# Precision_Arduino_Charlieplex_1_1.net
KiCad netlist of a schematic drawn in EAGLE
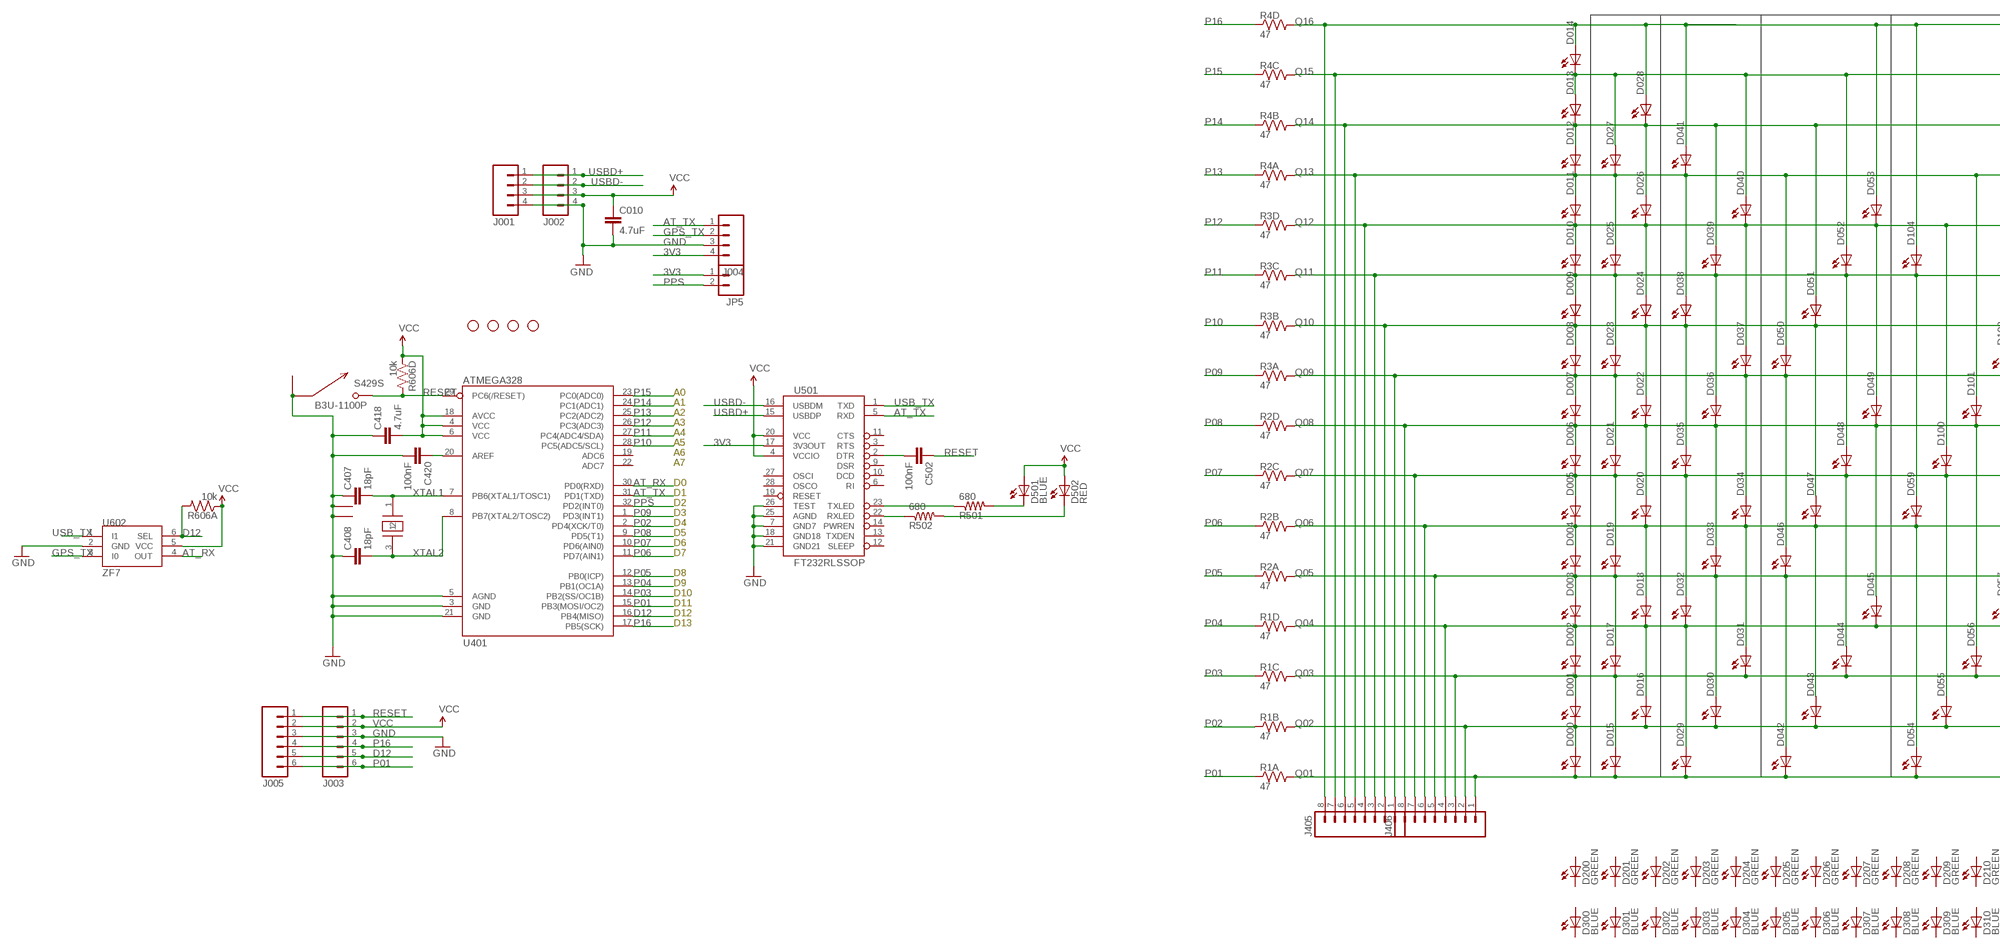
[diagram p0: schematic, sheet 1, part 1 of 2]
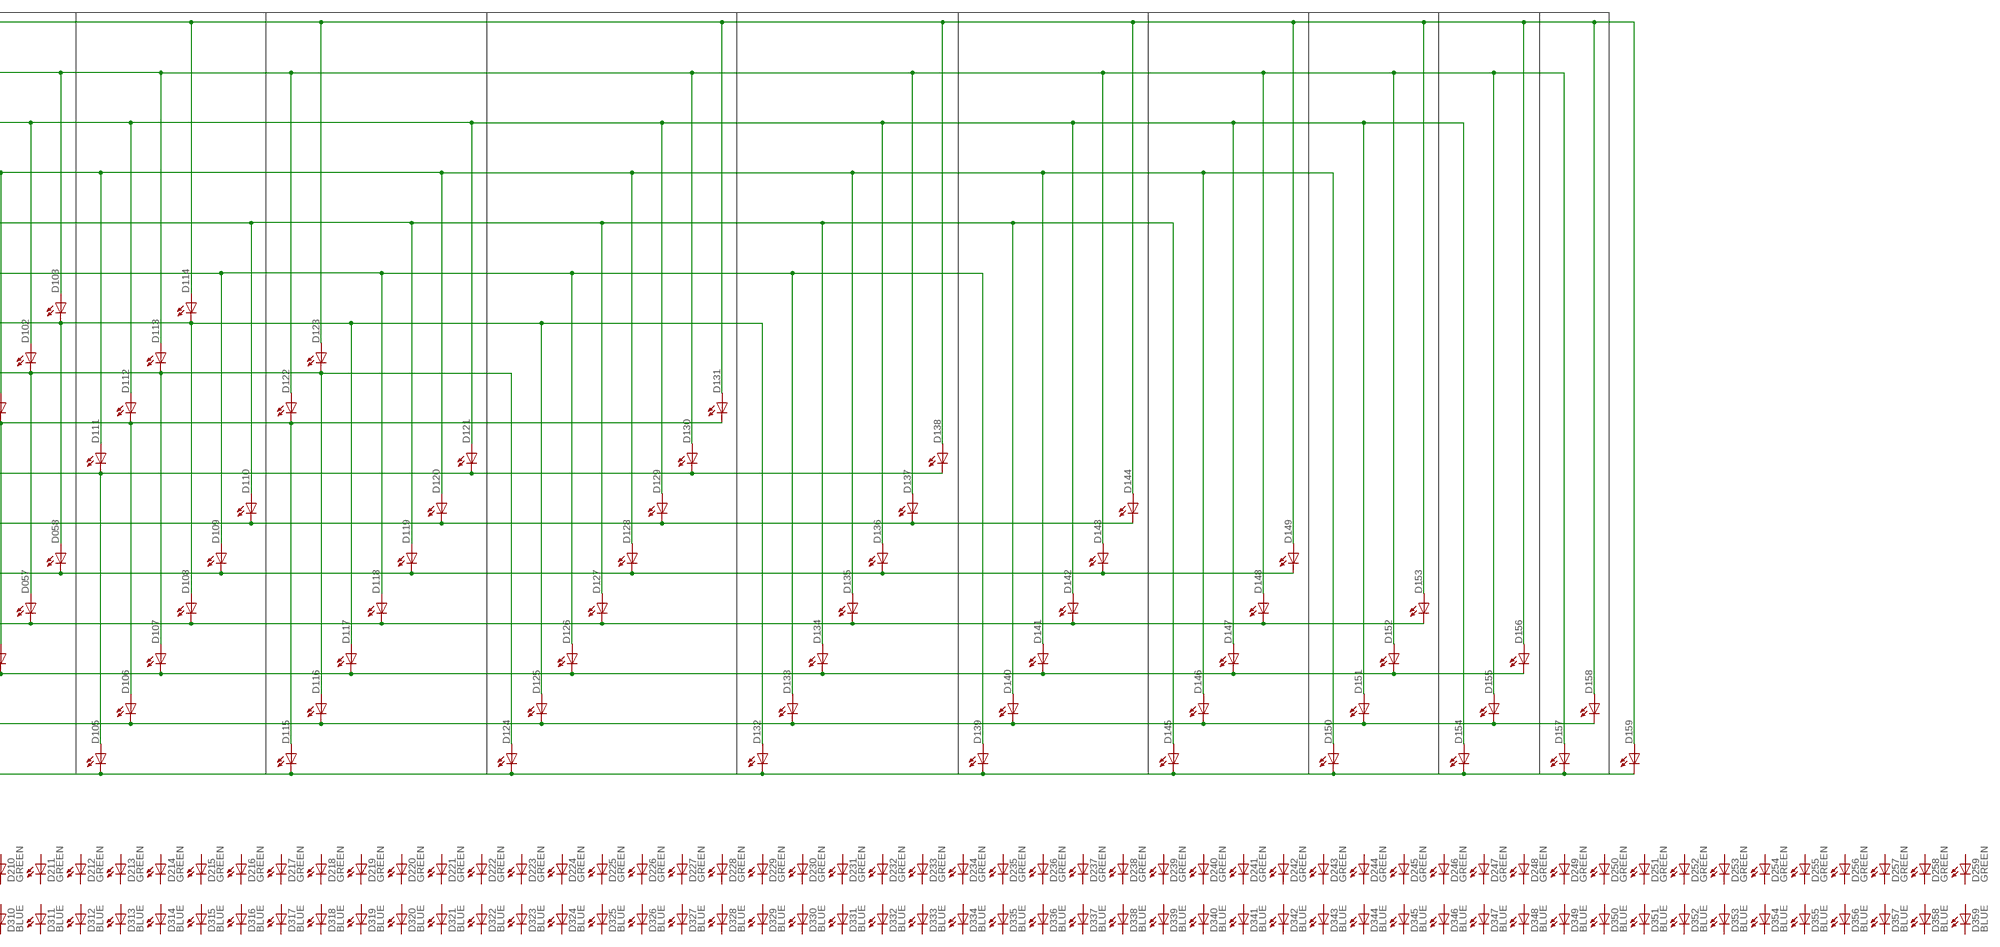
[diagram p1: schematic, sheet 1, part 2 of 2]

(export (version "E")
  (design (tool "Eeschema 10.0.6"))
  (components
    (comp (ref "C010")
      (value "4.7uF")
      (footprint "eagle-import:0603-CAP")
      (libsource (lib "eagle-import") (part "CAP0603-CAP"))
    )
    (comp (ref "C407")
      (value "18pF")
      (footprint "eagle-import:0603-CAP")
      (libsource (lib "eagle-import") (part "CAP0603-CAP"))
    )
    (comp (ref "C408")
      (value "18pF")
      (footprint "eagle-import:0603-CAP")
      (libsource (lib "eagle-import") (part "CAP0603-CAP"))
    )
    (comp (ref "C418")
      (value "4.7uF")
      (footprint "eagle-import:0603-CAP")
      (libsource (lib "eagle-import") (part "CAP0603-CAP"))
    )
    (comp (ref "C420")
      (value "100nF")
      (footprint "eagle-import:0603-CAP")
      (libsource (lib "eagle-import") (part "CAP0603-CAP"))
    )
    (comp (ref "C502")
      (value "100nF")
      (footprint "eagle-import:0603-CAP")
      (libsource (lib "eagle-import") (part "CAP0603-CAP"))
    )
    (comp (ref "D000")
      (value "RED")
      (footprint "eagle-import:LED-0603")
      (libsource (lib "eagle-import") (part "SparkFun-LED_LED0603"))
    )
    (comp (ref "D001")
      (value "RED")
      (footprint "eagle-import:LED-0603")
      (libsource (lib "eagle-import") (part "SparkFun-LED_LED0603"))
    )
    (comp (ref "D002")
      (value "RED")
      (footprint "eagle-import:LED-0603")
      (libsource (lib "eagle-import") (part "SparkFun-LED_LED0603"))
    )
    (comp (ref "D003")
      (value "RED")
      (footprint "eagle-import:LED-0603")
      (libsource (lib "eagle-import") (part "SparkFun-LED_LED0603"))
    )
    (comp (ref "D004")
      (value "RED")
      (footprint "eagle-import:LED-0603")
      (libsource (lib "eagle-import") (part "SparkFun-LED_LED0603"))
    )
    (comp (ref "D005")
      (value "RED")
      (footprint "eagle-import:LED-0603")
      (libsource (lib "eagle-import") (part "SparkFun-LED_LED0603"))
    )
    (comp (ref "D006")
      (value "RED")
      (footprint "eagle-import:LED-0603")
      (libsource (lib "eagle-import") (part "SparkFun-LED_LED0603"))
    )
    (comp (ref "D007")
      (value "RED")
      (footprint "eagle-import:LED-0603")
      (libsource (lib "eagle-import") (part "SparkFun-LED_LED0603"))
    )
    (comp (ref "D008")
      (value "RED")
      (footprint "eagle-import:LED-0603")
      (libsource (lib "eagle-import") (part "SparkFun-LED_LED0603"))
    )
    (comp (ref "D009")
      (value "RED")
      (footprint "eagle-import:LED-0603")
      (libsource (lib "eagle-import") (part "SparkFun-LED_LED0603"))
    )
    (comp (ref "D010")
      (value "RED")
      (footprint "eagle-import:LED-0603")
      (libsource (lib "eagle-import") (part "SparkFun-LED_LED0603"))
    )
    (comp (ref "D011")
      (value "RED")
      (footprint "eagle-import:LED-0603")
      (libsource (lib "eagle-import") (part "SparkFun-LED_LED0603"))
    )
    (comp (ref "D012")
      (value "RED")
      (footprint "eagle-import:LED-0603")
      (libsource (lib "eagle-import") (part "SparkFun-LED_LED0603"))
    )
    (comp (ref "D013")
      (value "RED")
      (footprint "eagle-import:LED-0603")
      (libsource (lib "eagle-import") (part "SparkFun-LED_LED0603"))
    )
    (comp (ref "D014")
      (value "RED")
      (footprint "eagle-import:LED-0603")
      (libsource (lib "eagle-import") (part "SparkFun-LED_LED0603"))
    )
    (comp (ref "D015")
      (value "RED")
      (footprint "eagle-import:LED-0603")
      (libsource (lib "eagle-import") (part "SparkFun-LED_LED0603"))
    )
    (comp (ref "D016")
      (value "RED")
      (footprint "eagle-import:LED-0603")
      (libsource (lib "eagle-import") (part "SparkFun-LED_LED0603"))
    )
    (comp (ref "D017")
      (value "RED")
      (footprint "eagle-import:LED-0603")
      (libsource (lib "eagle-import") (part "SparkFun-LED_LED0603"))
    )
    (comp (ref "D018")
      (value "RED")
      (footprint "eagle-import:LED-0603")
      (libsource (lib "eagle-import") (part "SparkFun-LED_LED0603"))
    )
    (comp (ref "D019")
      (value "RED")
      (footprint "eagle-import:LED-0603")
      (libsource (lib "eagle-import") (part "SparkFun-LED_LED0603"))
    )
    (comp (ref "D020")
      (value "RED")
      (footprint "eagle-import:LED-0603")
      (libsource (lib "eagle-import") (part "SparkFun-LED_LED0603"))
    )
    (comp (ref "D021")
      (value "RED")
      (footprint "eagle-import:LED-0603")
      (libsource (lib "eagle-import") (part "SparkFun-LED_LED0603"))
    )
    (comp (ref "D022")
      (value "RED")
      (footprint "eagle-import:LED-0603")
      (libsource (lib "eagle-import") (part "SparkFun-LED_LED0603"))
    )
    (comp (ref "D023")
      (value "RED")
      (footprint "eagle-import:LED-0603")
      (libsource (lib "eagle-import") (part "SparkFun-LED_LED0603"))
    )
    (comp (ref "D024")
      (value "RED")
      (footprint "eagle-import:LED-0603")
      (libsource (lib "eagle-import") (part "SparkFun-LED_LED0603"))
    )
    (comp (ref "D025")
      (value "RED")
      (footprint "eagle-import:LED-0603")
      (libsource (lib "eagle-import") (part "SparkFun-LED_LED0603"))
    )
    (comp (ref "D026")
      (value "RED")
      (footprint "eagle-import:LED-0603")
      (libsource (lib "eagle-import") (part "SparkFun-LED_LED0603"))
    )
    (comp (ref "D027")
      (value "RED")
      (footprint "eagle-import:LED-0603")
      (libsource (lib "eagle-import") (part "SparkFun-LED_LED0603"))
    )
    (comp (ref "D028")
      (value "RED")
      (footprint "eagle-import:LED-0603")
      (libsource (lib "eagle-import") (part "SparkFun-LED_LED0603"))
    )
    (comp (ref "D029")
      (value "RED")
      (footprint "eagle-import:LED-0603")
      (libsource (lib "eagle-import") (part "SparkFun-LED_LED0603"))
    )
    (comp (ref "D030")
      (value "RED")
      (footprint "eagle-import:LED-0603")
      (libsource (lib "eagle-import") (part "SparkFun-LED_LED0603"))
    )
    (comp (ref "D031")
      (value "RED")
      (footprint "eagle-import:LED-0603")
      (libsource (lib "eagle-import") (part "SparkFun-LED_LED0603"))
    )
    (comp (ref "D032")
      (value "RED")
      (footprint "eagle-import:LED-0603")
      (libsource (lib "eagle-import") (part "SparkFun-LED_LED0603"))
    )
    (comp (ref "D033")
      (value "RED")
      (footprint "eagle-import:LED-0603")
      (libsource (lib "eagle-import") (part "SparkFun-LED_LED0603"))
    )
    (comp (ref "D034")
      (value "RED")
      (footprint "eagle-import:LED-0603")
      (libsource (lib "eagle-import") (part "SparkFun-LED_LED0603"))
    )
    (comp (ref "D035")
      (value "RED")
      (footprint "eagle-import:LED-0603")
      (libsource (lib "eagle-import") (part "SparkFun-LED_LED0603"))
    )
    (comp (ref "D036")
      (value "RED")
      (footprint "eagle-import:LED-0603")
      (libsource (lib "eagle-import") (part "SparkFun-LED_LED0603"))
    )
    (comp (ref "D037")
      (value "RED")
      (footprint "eagle-import:LED-0603")
      (libsource (lib "eagle-import") (part "SparkFun-LED_LED0603"))
    )
    (comp (ref "D038")
      (value "RED")
      (footprint "eagle-import:LED-0603")
      (libsource (lib "eagle-import") (part "SparkFun-LED_LED0603"))
    )
    (comp (ref "D039")
      (value "RED")
      (footprint "eagle-import:LED-0603")
      (libsource (lib "eagle-import") (part "SparkFun-LED_LED0603"))
    )
    (comp (ref "D040")
      (value "RED")
      (footprint "eagle-import:LED-0603")
      (libsource (lib "eagle-import") (part "SparkFun-LED_LED0603"))
    )
    (comp (ref "D041")
      (value "RED")
      (footprint "eagle-import:LED-0603")
      (libsource (lib "eagle-import") (part "SparkFun-LED_LED0603"))
    )
    (comp (ref "D042")
      (value "RED")
      (footprint "eagle-import:LED-0603")
      (libsource (lib "eagle-import") (part "SparkFun-LED_LED0603"))
    )
    (comp (ref "D043")
      (value "RED")
      (footprint "eagle-import:LED-0603")
      (libsource (lib "eagle-import") (part "SparkFun-LED_LED0603"))
    )
    (comp (ref "D044")
      (value "RED")
      (footprint "eagle-import:LED-0603")
      (libsource (lib "eagle-import") (part "SparkFun-LED_LED0603"))
    )
    (comp (ref "D045")
      (value "RED")
      (footprint "eagle-import:LED-0603")
      (libsource (lib "eagle-import") (part "SparkFun-LED_LED0603"))
    )
    (comp (ref "D046")
      (value "RED")
      (footprint "eagle-import:LED-0603")
      (libsource (lib "eagle-import") (part "SparkFun-LED_LED0603"))
    )
    (comp (ref "D047")
      (value "RED")
      (footprint "eagle-import:LED-0603")
      (libsource (lib "eagle-import") (part "SparkFun-LED_LED0603"))
    )
    (comp (ref "D048")
      (value "RED")
      (footprint "eagle-import:LED-0603")
      (libsource (lib "eagle-import") (part "SparkFun-LED_LED0603"))
    )
    (comp (ref "D049")
      (value "RED")
      (footprint "eagle-import:LED-0603")
      (libsource (lib "eagle-import") (part "SparkFun-LED_LED0603"))
    )
    (comp (ref "D050")
      (value "RED")
      (footprint "eagle-import:LED-0603")
      (libsource (lib "eagle-import") (part "SparkFun-LED_LED0603"))
    )
    (comp (ref "D051")
      (value "RED")
      (footprint "eagle-import:LED-0603")
      (libsource (lib "eagle-import") (part "SparkFun-LED_LED0603"))
    )
    (comp (ref "D052")
      (value "RED")
      (footprint "eagle-import:LED-0603")
      (libsource (lib "eagle-import") (part "SparkFun-LED_LED0603"))
    )
    (comp (ref "D053")
      (value "RED")
      (footprint "eagle-import:LED-0603")
      (libsource (lib "eagle-import") (part "SparkFun-LED_LED0603"))
    )
    (comp (ref "D054")
      (value "RED")
      (footprint "eagle-import:LED-0603")
      (libsource (lib "eagle-import") (part "SparkFun-LED_LED0603"))
    )
    (comp (ref "D055")
      (value "RED")
      (footprint "eagle-import:LED-0603")
      (libsource (lib "eagle-import") (part "SparkFun-LED_LED0603"))
    )
    (comp (ref "D056")
      (value "RED")
      (footprint "eagle-import:LED-0603")
      (libsource (lib "eagle-import") (part "SparkFun-LED_LED0603"))
    )
    (comp (ref "D057")
      (value "RED")
      (footprint "eagle-import:LED-0603")
      (libsource (lib "eagle-import") (part "SparkFun-LED_LED0603"))
    )
    (comp (ref "D058")
      (value "RED")
      (footprint "eagle-import:LED-0603")
      (libsource (lib "eagle-import") (part "SparkFun-LED_LED0603"))
    )
    (comp (ref "D059")
      (value "RED")
      (footprint "eagle-import:LED-0603")
      (libsource (lib "eagle-import") (part "SparkFun-LED_LED0603"))
    )
    (comp (ref "D100")
      (value "YELLOW")
      (footprint "eagle-import:LED-0603")
      (libsource (lib "eagle-import") (part "SparkFun-LED_LED0603"))
    )
    (comp (ref "D101")
      (value "YELLOW")
      (footprint "eagle-import:LED-0603")
      (libsource (lib "eagle-import") (part "SparkFun-LED_LED0603"))
    )
    (comp (ref "D102")
      (value "YELLOW")
      (footprint "eagle-import:LED-0603")
      (libsource (lib "eagle-import") (part "SparkFun-LED_LED0603"))
    )
    (comp (ref "D103")
      (value "YELLOW")
      (footprint "eagle-import:LED-0603")
      (libsource (lib "eagle-import") (part "SparkFun-LED_LED0603"))
    )
    (comp (ref "D104")
      (value "YELLOW")
      (footprint "eagle-import:LED-0603")
      (libsource (lib "eagle-import") (part "SparkFun-LED_LED0603"))
    )
    (comp (ref "D105")
      (value "YELLOW")
      (footprint "eagle-import:LED-0603")
      (libsource (lib "eagle-import") (part "SparkFun-LED_LED0603"))
    )
    (comp (ref "D106")
      (value "YELLOW")
      (footprint "eagle-import:LED-0603")
      (libsource (lib "eagle-import") (part "SparkFun-LED_LED0603"))
    )
    (comp (ref "D107")
      (value "YELLOW")
      (footprint "eagle-import:LED-0603")
      (libsource (lib "eagle-import") (part "SparkFun-LED_LED0603"))
    )
    (comp (ref "D108")
      (value "YELLOW")
      (footprint "eagle-import:LED-0603")
      (libsource (lib "eagle-import") (part "SparkFun-LED_LED0603"))
    )
    (comp (ref "D109")
      (value "YELLOW")
      (footprint "eagle-import:LED-0603")
      (libsource (lib "eagle-import") (part "SparkFun-LED_LED0603"))
    )
    (comp (ref "D110")
      (value "YELLOW")
      (footprint "eagle-import:LED-0603")
      (libsource (lib "eagle-import") (part "SparkFun-LED_LED0603"))
    )
    (comp (ref "D111")
      (value "YELLOW")
      (footprint "eagle-import:LED-0603")
      (libsource (lib "eagle-import") (part "SparkFun-LED_LED0603"))
    )
    (comp (ref "D112")
      (value "YELLOW")
      (footprint "eagle-import:LED-0603")
      (libsource (lib "eagle-import") (part "SparkFun-LED_LED0603"))
    )
    (comp (ref "D113")
      (value "YELLOW")
      (footprint "eagle-import:LED-0603")
      (libsource (lib "eagle-import") (part "SparkFun-LED_LED0603"))
    )
    (comp (ref "D114")
      (value "YELLOW")
      (footprint "eagle-import:LED-0603")
      (libsource (lib "eagle-import") (part "SparkFun-LED_LED0603"))
    )
    (comp (ref "D115")
      (value "YELLOW")
      (footprint "eagle-import:LED-0603")
      (libsource (lib "eagle-import") (part "SparkFun-LED_LED0603"))
    )
    (comp (ref "D116")
      (value "YELLOW")
      (footprint "eagle-import:LED-0603")
      (libsource (lib "eagle-import") (part "SparkFun-LED_LED0603"))
    )
    (comp (ref "D117")
      (value "YELLOW")
      (footprint "eagle-import:LED-0603")
      (libsource (lib "eagle-import") (part "SparkFun-LED_LED0603"))
    )
    (comp (ref "D118")
      (value "YELLOW")
      (footprint "eagle-import:LED-0603")
      (libsource (lib "eagle-import") (part "SparkFun-LED_LED0603"))
    )
    (comp (ref "D119")
      (value "YELLOW")
      (footprint "eagle-import:LED-0603")
      (libsource (lib "eagle-import") (part "SparkFun-LED_LED0603"))
    )
    (comp (ref "D120")
      (value "YELLOW")
      (footprint "eagle-import:LED-0603")
      (libsource (lib "eagle-import") (part "SparkFun-LED_LED0603"))
    )
    (comp (ref "D121")
      (value "YELLOW")
      (footprint "eagle-import:LED-0603")
      (libsource (lib "eagle-import") (part "SparkFun-LED_LED0603"))
    )
    (comp (ref "D122")
      (value "YELLOW")
      (footprint "eagle-import:LED-0603")
      (libsource (lib "eagle-import") (part "SparkFun-LED_LED0603"))
    )
    (comp (ref "D123")
      (value "YELLOW")
      (footprint "eagle-import:LED-0603")
      (libsource (lib "eagle-import") (part "SparkFun-LED_LED0603"))
    )
    (comp (ref "D124")
      (value "YELLOW")
      (footprint "eagle-import:LED-0603")
      (libsource (lib "eagle-import") (part "SparkFun-LED_LED0603"))
    )
    (comp (ref "D125")
      (value "YELLOW")
      (footprint "eagle-import:LED-0603")
      (libsource (lib "eagle-import") (part "SparkFun-LED_LED0603"))
    )
    (comp (ref "D126")
      (value "YELLOW")
      (footprint "eagle-import:LED-0603")
      (libsource (lib "eagle-import") (part "SparkFun-LED_LED0603"))
    )
    (comp (ref "D127")
      (value "YELLOW")
      (footprint "eagle-import:LED-0603")
      (libsource (lib "eagle-import") (part "SparkFun-LED_LED0603"))
    )
    (comp (ref "D128")
      (value "YELLOW")
      (footprint "eagle-import:LED-0603")
      (libsource (lib "eagle-import") (part "SparkFun-LED_LED0603"))
    )
    (comp (ref "D129")
      (value "YELLOW")
      (footprint "eagle-import:LED-0603")
      (libsource (lib "eagle-import") (part "SparkFun-LED_LED0603"))
    )
    (comp (ref "D130")
      (value "YELLOW")
      (footprint "eagle-import:LED-0603")
      (libsource (lib "eagle-import") (part "SparkFun-LED_LED0603"))
    )
    (comp (ref "D131")
      (value "YELLOW")
      (footprint "eagle-import:LED-0603")
      (libsource (lib "eagle-import") (part "SparkFun-LED_LED0603"))
    )
    (comp (ref "D132")
      (value "YELLOW")
      (footprint "eagle-import:LED-0603")
      (libsource (lib "eagle-import") (part "SparkFun-LED_LED0603"))
    )
    (comp (ref "D133")
      (value "YELLOW")
      (footprint "eagle-import:LED-0603")
      (libsource (lib "eagle-import") (part "SparkFun-LED_LED0603"))
    )
    (comp (ref "D134")
      (value "YELLOW")
      (footprint "eagle-import:LED-0603")
      (libsource (lib "eagle-import") (part "SparkFun-LED_LED0603"))
    )
    (comp (ref "D135")
      (value "YELLOW")
      (footprint "eagle-import:LED-0603")
      (libsource (lib "eagle-import") (part "SparkFun-LED_LED0603"))
    )
    (comp (ref "D136")
      (value "YELLOW")
      (footprint "eagle-import:LED-0603")
      (libsource (lib "eagle-import") (part "SparkFun-LED_LED0603"))
    )
    (comp (ref "D137")
      (value "YELLOW")
      (footprint "eagle-import:LED-0603")
      (libsource (lib "eagle-import") (part "SparkFun-LED_LED0603"))
    )
    (comp (ref "D138")
      (value "YELLOW")
      (footprint "eagle-import:LED-0603")
      (libsource (lib "eagle-import") (part "SparkFun-LED_LED0603"))
    )
    (comp (ref "D139")
      (value "YELLOW")
      (footprint "eagle-import:LED-0603")
      (libsource (lib "eagle-import") (part "SparkFun-LED_LED0603"))
    )
    (comp (ref "D140")
      (value "YELLOW")
      (footprint "eagle-import:LED-0603")
      (libsource (lib "eagle-import") (part "SparkFun-LED_LED0603"))
    )
    (comp (ref "D141")
      (value "YELLOW")
      (footprint "eagle-import:LED-0603")
      (libsource (lib "eagle-import") (part "SparkFun-LED_LED0603"))
    )
    (comp (ref "D142")
      (value "YELLOW")
      (footprint "eagle-import:LED-0603")
      (libsource (lib "eagle-import") (part "SparkFun-LED_LED0603"))
    )
    (comp (ref "D143")
      (value "YELLOW")
      (footprint "eagle-import:LED-0603")
      (libsource (lib "eagle-import") (part "SparkFun-LED_LED0603"))
    )
    (comp (ref "D144")
      (value "YELLOW")
      (footprint "eagle-import:LED-0603")
      (libsource (lib "eagle-import") (part "SparkFun-LED_LED0603"))
    )
    (comp (ref "D145")
      (value "YELLOW")
      (footprint "eagle-import:LED-0603")
      (libsource (lib "eagle-import") (part "SparkFun-LED_LED0603"))
    )
    (comp (ref "D146")
      (value "YELLOW")
      (footprint "eagle-import:LED-0603")
      (libsource (lib "eagle-import") (part "SparkFun-LED_LED0603"))
    )
    (comp (ref "D147")
      (value "YELLOW")
      (footprint "eagle-import:LED-0603")
      (libsource (lib "eagle-import") (part "SparkFun-LED_LED0603"))
    )
    (comp (ref "D148")
      (value "YELLOW")
      (footprint "eagle-import:LED-0603")
      (libsource (lib "eagle-import") (part "SparkFun-LED_LED0603"))
    )
    (comp (ref "D149")
      (value "YELLOW")
      (footprint "eagle-import:LED-0603")
      (libsource (lib "eagle-import") (part "SparkFun-LED_LED0603"))
    )
    (comp (ref "D150")
      (value "YELLOW")
      (footprint "eagle-import:LED-0603")
      (libsource (lib "eagle-import") (part "SparkFun-LED_LED0603"))
    )
    (comp (ref "D151")
      (value "YELLOW")
      (footprint "eagle-import:LED-0603")
      (libsource (lib "eagle-import") (part "SparkFun-LED_LED0603"))
    )
    (comp (ref "D152")
      (value "YELLOW")
      (footprint "eagle-import:LED-0603")
      (libsource (lib "eagle-import") (part "SparkFun-LED_LED0603"))
    )
    (comp (ref "D153")
      (value "YELLOW")
      (footprint "eagle-import:LED-0603")
      (libsource (lib "eagle-import") (part "SparkFun-LED_LED0603"))
    )
    (comp (ref "D154")
      (value "YELLOW")
      (footprint "eagle-import:LED-0603")
      (libsource (lib "eagle-import") (part "SparkFun-LED_LED0603"))
    )
    (comp (ref "D155")
      (value "YELLOW")
      (footprint "eagle-import:LED-0603")
      (libsource (lib "eagle-import") (part "SparkFun-LED_LED0603"))
    )
    (comp (ref "D156")
      (value "YELLOW")
      (footprint "eagle-import:LED-0603")
      (libsource (lib "eagle-import") (part "SparkFun-LED_LED0603"))
    )
    (comp (ref "D157")
      (value "YELLOW")
      (footprint "eagle-import:LED-0603")
      (libsource (lib "eagle-import") (part "SparkFun-LED_LED0603"))
    )
    (comp (ref "D158")
      (value "YELLOW")
      (footprint "eagle-import:LED-0603")
      (libsource (lib "eagle-import") (part "SparkFun-LED_LED0603"))
    )
    (comp (ref "D159")
      (value "YELLOW")
      (footprint "eagle-import:LED-0603")
      (libsource (lib "eagle-import") (part "SparkFun-LED_LED0603"))
    )
    (comp (ref "D200")
      (value "GREEN")
      (footprint "eagle-import:LED-0603")
      (libsource (lib "eagle-import") (part "SparkFun-LED_LED0603"))
    )
    (comp (ref "D201")
      (value "GREEN")
      (footprint "eagle-import:LED-0603")
      (libsource (lib "eagle-import") (part "SparkFun-LED_LED0603"))
    )
    (comp (ref "D202")
      (value "GREEN")
      (footprint "eagle-import:LED-0603")
      (libsource (lib "eagle-import") (part "SparkFun-LED_LED0603"))
    )
    (comp (ref "D203")
      (value "GREEN")
      (footprint "eagle-import:LED-0603")
      (libsource (lib "eagle-import") (part "SparkFun-LED_LED0603"))
    )
    (comp (ref "D204")
      (value "GREEN")
      (footprint "eagle-import:LED-0603")
      (libsource (lib "eagle-import") (part "SparkFun-LED_LED0603"))
    )
    (comp (ref "D205")
      (value "GREEN")
      (footprint "eagle-import:LED-0603")
      (libsource (lib "eagle-import") (part "SparkFun-LED_LED0603"))
    )
    (comp (ref "D206")
      (value "GREEN")
      (footprint "eagle-import:LED-0603")
      (libsource (lib "eagle-import") (part "SparkFun-LED_LED0603"))
    )
    (comp (ref "D207")
      (value "GREEN")
      (footprint "eagle-import:LED-0603")
      (libsource (lib "eagle-import") (part "SparkFun-LED_LED0603"))
    )
    (comp (ref "D208")
      (value "GREEN")
      (footprint "eagle-import:LED-0603")
      (libsource (lib "eagle-import") (part "SparkFun-LED_LED0603"))
    )
    (comp (ref "D209")
      (value "GREEN")
      (footprint "eagle-import:LED-0603")
      (libsource (lib "eagle-import") (part "SparkFun-LED_LED0603"))
    )
    (comp (ref "D210")
      (value "GREEN")
      (footprint "eagle-import:LED-0603")
      (libsource (lib "eagle-import") (part "SparkFun-LED_LED0603"))
    )
    (comp (ref "D211")
      (value "GREEN")
      (footprint "eagle-import:LED-0603")
      (libsource (lib "eagle-import") (part "SparkFun-LED_LED0603"))
    )
    (comp (ref "D212")
      (value "GREEN")
      (footprint "eagle-import:LED-0603")
      (libsource (lib "eagle-import") (part "SparkFun-LED_LED0603"))
    )
    (comp (ref "D213")
      (value "GREEN")
      (footprint "eagle-import:LED-0603")
      (libsource (lib "eagle-import") (part "SparkFun-LED_LED0603"))
    )
    (comp (ref "D214")
      (value "GREEN")
      (footprint "eagle-import:LED-0603")
      (libsource (lib "eagle-import") (part "SparkFun-LED_LED0603"))
    )
    (comp (ref "D215")
      (value "GREEN")
      (footprint "eagle-import:LED-0603")
      (libsource (lib "eagle-import") (part "SparkFun-LED_LED0603"))
    )
    (comp (ref "D216")
      (value "GREEN")
      (footprint "eagle-import:LED-0603")
      (libsource (lib "eagle-import") (part "SparkFun-LED_LED0603"))
    )
    (comp (ref "D217")
      (value "GREEN")
      (footprint "eagle-import:LED-0603")
      (libsource (lib "eagle-import") (part "SparkFun-LED_LED0603"))
    )
    (comp (ref "D218")
      (value "GREEN")
      (footprint "eagle-import:LED-0603")
      (libsource (lib "eagle-import") (part "SparkFun-LED_LED0603"))
    )
    (comp (ref "D219")
      (value "GREEN")
      (footprint "eagle-import:LED-0603")
      (libsource (lib "eagle-import") (part "SparkFun-LED_LED0603"))
    )
    (comp (ref "D220")
      (value "GREEN")
      (footprint "eagle-import:LED-0603")
      (libsource (lib "eagle-import") (part "SparkFun-LED_LED0603"))
    )
    (comp (ref "D221")
      (value "GREEN")
      (footprint "eagle-import:LED-0603")
      (libsource (lib "eagle-import") (part "SparkFun-LED_LED0603"))
    )
    (comp (ref "D222")
      (value "GREEN")
      (footprint "eagle-import:LED-0603")
      (libsource (lib "eagle-import") (part "SparkFun-LED_LED0603"))
    )
    (comp (ref "D223")
      (value "GREEN")
      (footprint "eagle-import:LED-0603")
      (libsource (lib "eagle-import") (part "SparkFun-LED_LED0603"))
    )
    (comp (ref "D224")
      (value "GREEN")
      (footprint "eagle-import:LED-0603")
      (libsource (lib "eagle-import") (part "SparkFun-LED_LED0603"))
    )
    (comp (ref "D225")
      (value "GREEN")
      (footprint "eagle-import:LED-0603")
      (libsource (lib "eagle-import") (part "SparkFun-LED_LED0603"))
    )
    (comp (ref "D226")
      (value "GREEN")
      (footprint "eagle-import:LED-0603")
      (libsource (lib "eagle-import") (part "SparkFun-LED_LED0603"))
    )
    (comp (ref "D227")
      (value "GREEN")
      (footprint "eagle-import:LED-0603")
      (libsource (lib "eagle-import") (part "SparkFun-LED_LED0603"))
    )
    (comp (ref "D228")
      (value "GREEN")
      (footprint "eagle-import:LED-0603")
      (libsource (lib "eagle-import") (part "SparkFun-LED_LED0603"))
    )
    (comp (ref "D229")
      (value "GREEN")
      (footprint "eagle-import:LED-0603")
      (libsource (lib "eagle-import") (part "SparkFun-LED_LED0603"))
    )
    (comp (ref "D230")
      (value "GREEN")
      (footprint "eagle-import:LED-0603")
      (libsource (lib "eagle-import") (part "SparkFun-LED_LED0603"))
    )
    (comp (ref "D231")
      (value "GREEN")
      (footprint "eagle-import:LED-0603")
      (libsource (lib "eagle-import") (part "SparkFun-LED_LED0603"))
    )
    (comp (ref "D232")
      (value "GREEN")
      (footprint "eagle-import:LED-0603")
      (libsource (lib "eagle-import") (part "SparkFun-LED_LED0603"))
    )
    (comp (ref "D233")
      (value "GREEN")
      (footprint "eagle-import:LED-0603")
      (libsource (lib "eagle-import") (part "SparkFun-LED_LED0603"))
    )
    (comp (ref "D234")
      (value "GREEN")
      (footprint "eagle-import:LED-0603")
      (libsource (lib "eagle-import") (part "SparkFun-LED_LED0603"))
    )
    (comp (ref "D235")
      (value "GREEN")
      (footprint "eagle-import:LED-0603")
      (libsource (lib "eagle-import") (part "SparkFun-LED_LED0603"))
    )
    (comp (ref "D236")
      (value "GREEN")
      (footprint "eagle-import:LED-0603")
      (libsource (lib "eagle-import") (part "SparkFun-LED_LED0603"))
    )
    (comp (ref "D237")
      (value "GREEN")
      (footprint "eagle-import:LED-0603")
      (libsource (lib "eagle-import") (part "SparkFun-LED_LED0603"))
    )
    (comp (ref "D238")
      (value "GREEN")
      (footprint "eagle-import:LED-0603")
      (libsource (lib "eagle-import") (part "SparkFun-LED_LED0603"))
    )
    (comp (ref "D239")
      (value "GREEN")
      (footprint "eagle-import:LED-0603")
      (libsource (lib "eagle-import") (part "SparkFun-LED_LED0603"))
    )
    (comp (ref "D240")
      (value "GREEN")
      (footprint "eagle-import:LED-0603")
      (libsource (lib "eagle-import") (part "SparkFun-LED_LED0603"))
    )
    (comp (ref "D241")
      (value "GREEN")
      (footprint "eagle-import:LED-0603")
      (libsource (lib "eagle-import") (part "SparkFun-LED_LED0603"))
    )
    (comp (ref "D242")
      (value "GREEN")
      (footprint "eagle-import:LED-0603")
      (libsource (lib "eagle-import") (part "SparkFun-LED_LED0603"))
    )
    (comp (ref "D243")
      (value "GREEN")
      (footprint "eagle-import:LED-0603")
      (libsource (lib "eagle-import") (part "SparkFun-LED_LED0603"))
    )
    (comp (ref "D244")
      (value "GREEN")
      (footprint "eagle-import:LED-0603")
      (libsource (lib "eagle-import") (part "SparkFun-LED_LED0603"))
    )
    (comp (ref "D245")
      (value "GREEN")
      (footprint "eagle-import:LED-0603")
      (libsource (lib "eagle-import") (part "SparkFun-LED_LED0603"))
    )
    (comp (ref "D246")
      (value "GREEN")
      (footprint "eagle-import:LED-0603")
      (libsource (lib "eagle-import") (part "SparkFun-LED_LED0603"))
    )
    (comp (ref "D247")
      (value "GREEN")
      (footprint "eagle-import:LED-0603")
      (libsource (lib "eagle-import") (part "SparkFun-LED_LED0603"))
    )
    (comp (ref "D248")
      (value "GREEN")
      (footprint "eagle-import:LED-0603")
      (libsource (lib "eagle-import") (part "SparkFun-LED_LED0603"))
    )
    (comp (ref "D249")
      (value "GREEN")
      (footprint "eagle-import:LED-0603")
      (libsource (lib "eagle-import") (part "SparkFun-LED_LED0603"))
    )
    (comp (ref "D250")
      (value "GREEN")
      (footprint "eagle-import:LED-0603")
      (libsource (lib "eagle-import") (part "SparkFun-LED_LED0603"))
    )
    (comp (ref "D251")
      (value "GREEN")
      (footprint "eagle-import:LED-0603")
      (libsource (lib "eagle-import") (part "SparkFun-LED_LED0603"))
    )
    (comp (ref "D252")
      (value "GREEN")
      (footprint "eagle-import:LED-0603")
      (libsource (lib "eagle-import") (part "SparkFun-LED_LED0603"))
    )
    (comp (ref "D253")
      (value "GREEN")
      (footprint "eagle-import:LED-0603")
      (libsource (lib "eagle-import") (part "SparkFun-LED_LED0603"))
    )
    (comp (ref "D254")
      (value "GREEN")
      (footprint "eagle-import:LED-0603")
      (libsource (lib "eagle-import") (part "SparkFun-LED_LED0603"))
    )
    (comp (ref "D255")
      (value "GREEN")
      (footprint "eagle-import:LED-0603")
      (libsource (lib "eagle-import") (part "SparkFun-LED_LED0603"))
    )
    (comp (ref "D256")
      (value "GREEN")
      (footprint "eagle-import:LED-0603")
      (libsource (lib "eagle-import") (part "SparkFun-LED_LED0603"))
    )
    (comp (ref "D257")
      (value "GREEN")
      (footprint "eagle-import:LED-0603")
      (libsource (lib "eagle-import") (part "SparkFun-LED_LED0603"))
    )
    (comp (ref "D258")
      (value "GREEN")
      (footprint "eagle-import:LED-0603")
      (libsource (lib "eagle-import") (part "SparkFun-LED_LED0603"))
    )
    (comp (ref "D259")
      (value "GREEN")
      (footprint "eagle-import:LED-0603")
      (libsource (lib "eagle-import") (part "SparkFun-LED_LED0603"))
    )
    (comp (ref "D300")
      (value "BLUE")
      (footprint "eagle-import:LED-0603")
      (libsource (lib "eagle-import") (part "SparkFun-LED_LED0603"))
    )
    (comp (ref "D301")
      (value "BLUE")
      (footprint "eagle-import:LED-0603")
      (libsource (lib "eagle-import") (part "SparkFun-LED_LED0603"))
    )
    (comp (ref "D302")
      (value "BLUE")
      (footprint "eagle-import:LED-0603")
      (libsource (lib "eagle-import") (part "SparkFun-LED_LED0603"))
    )
    (comp (ref "D303")
      (value "BLUE")
      (footprint "eagle-import:LED-0603")
      (libsource (lib "eagle-import") (part "SparkFun-LED_LED0603"))
    )
    (comp (ref "D304")
      (value "BLUE")
      (footprint "eagle-import:LED-0603")
      (libsource (lib "eagle-import") (part "SparkFun-LED_LED0603"))
    )
    (comp (ref "D305")
      (value "BLUE")
      (footprint "eagle-import:LED-0603")
      (libsource (lib "eagle-import") (part "SparkFun-LED_LED0603"))
    )
    (comp (ref "D306")
      (value "BLUE")
      (footprint "eagle-import:LED-0603")
      (libsource (lib "eagle-import") (part "SparkFun-LED_LED0603"))
    )
    (comp (ref "D307")
      (value "BLUE")
      (footprint "eagle-import:LED-0603")
      (libsource (lib "eagle-import") (part "SparkFun-LED_LED0603"))
    )
    (comp (ref "D308")
      (value "BLUE")
      (footprint "eagle-import:LED-0603")
      (libsource (lib "eagle-import") (part "SparkFun-LED_LED0603"))
    )
    (comp (ref "D309")
      (value "BLUE")
      (footprint "eagle-import:LED-0603")
      (libsource (lib "eagle-import") (part "SparkFun-LED_LED0603"))
    )
    (comp (ref "D310")
      (value "BLUE")
      (footprint "eagle-import:LED-0603")
      (libsource (lib "eagle-import") (part "SparkFun-LED_LED0603"))
    )
    (comp (ref "D311")
      (value "BLUE")
      (footprint "eagle-import:LED-0603")
      (libsource (lib "eagle-import") (part "SparkFun-LED_LED0603"))
    )
    (comp (ref "D312")
      (value "BLUE")
      (footprint "eagle-import:LED-0603")
      (libsource (lib "eagle-import") (part "SparkFun-LED_LED0603"))
    )
    (comp (ref "D313")
      (value "BLUE")
      (footprint "eagle-import:LED-0603")
      (libsource (lib "eagle-import") (part "SparkFun-LED_LED0603"))
    )
    (comp (ref "D314")
      (value "BLUE")
      (footprint "eagle-import:LED-0603")
      (libsource (lib "eagle-import") (part "SparkFun-LED_LED0603"))
    )
    (comp (ref "D315")
      (value "BLUE")
      (footprint "eagle-import:LED-0603")
      (libsource (lib "eagle-import") (part "SparkFun-LED_LED0603"))
    )
    (comp (ref "D316")
      (value "BLUE")
      (footprint "eagle-import:LED-0603")
      (libsource (lib "eagle-import") (part "SparkFun-LED_LED0603"))
    )
    (comp (ref "D317")
      (value "BLUE")
      (footprint "eagle-import:LED-0603")
      (libsource (lib "eagle-import") (part "SparkFun-LED_LED0603"))
    )
    (comp (ref "D318")
      (value "BLUE")
      (footprint "eagle-import:LED-0603")
      (libsource (lib "eagle-import") (part "SparkFun-LED_LED0603"))
    )
    (comp (ref "D319")
      (value "BLUE")
      (footprint "eagle-import:LED-0603")
      (libsource (lib "eagle-import") (part "SparkFun-LED_LED0603"))
    )
    (comp (ref "D320")
      (value "BLUE")
      (footprint "eagle-import:LED-0603")
      (libsource (lib "eagle-import") (part "SparkFun-LED_LED0603"))
    )
    (comp (ref "D321")
      (value "BLUE")
      (footprint "eagle-import:LED-0603")
      (libsource (lib "eagle-import") (part "SparkFun-LED_LED0603"))
    )
    (comp (ref "D322")
      (value "BLUE")
      (footprint "eagle-import:LED-0603")
      (libsource (lib "eagle-import") (part "SparkFun-LED_LED0603"))
    )
    (comp (ref "D323")
      (value "BLUE")
      (footprint "eagle-import:LED-0603")
      (libsource (lib "eagle-import") (part "SparkFun-LED_LED0603"))
    )
    (comp (ref "D324")
      (value "BLUE")
      (footprint "eagle-import:LED-0603")
      (libsource (lib "eagle-import") (part "SparkFun-LED_LED0603"))
    )
    (comp (ref "D325")
      (value "BLUE")
      (footprint "eagle-import:LED-0603")
      (libsource (lib "eagle-import") (part "SparkFun-LED_LED0603"))
    )
    (comp (ref "D326")
      (value "BLUE")
      (footprint "eagle-import:LED-0603")
      (libsource (lib "eagle-import") (part "SparkFun-LED_LED0603"))
    )
    (comp (ref "D327")
      (value "BLUE")
      (footprint "eagle-import:LED-0603")
      (libsource (lib "eagle-import") (part "SparkFun-LED_LED0603"))
    )
    (comp (ref "D328")
      (value "BLUE")
      (footprint "eagle-import:LED-0603")
      (libsource (lib "eagle-import") (part "SparkFun-LED_LED0603"))
    )
    (comp (ref "D329")
      (value "BLUE")
      (footprint "eagle-import:LED-0603")
      (libsource (lib "eagle-import") (part "SparkFun-LED_LED0603"))
    )
    (comp (ref "D330")
      (value "BLUE")
      (footprint "eagle-import:LED-0603")
      (libsource (lib "eagle-import") (part "SparkFun-LED_LED0603"))
    )
    (comp (ref "D331")
      (value "BLUE")
      (footprint "eagle-import:LED-0603")
      (libsource (lib "eagle-import") (part "SparkFun-LED_LED0603"))
    )
    (comp (ref "D332")
      (value "BLUE")
      (footprint "eagle-import:LED-0603")
      (libsource (lib "eagle-import") (part "SparkFun-LED_LED0603"))
    )
    (comp (ref "D333")
      (value "BLUE")
      (footprint "eagle-import:LED-0603")
      (libsource (lib "eagle-import") (part "SparkFun-LED_LED0603"))
    )
    (comp (ref "D334")
      (value "BLUE")
      (footprint "eagle-import:LED-0603")
      (libsource (lib "eagle-import") (part "SparkFun-LED_LED0603"))
    )
    (comp (ref "D335")
      (value "BLUE")
      (footprint "eagle-import:LED-0603")
      (libsource (lib "eagle-import") (part "SparkFun-LED_LED0603"))
    )
    (comp (ref "D336")
      (value "BLUE")
      (footprint "eagle-import:LED-0603")
      (libsource (lib "eagle-import") (part "SparkFun-LED_LED0603"))
    )
    (comp (ref "D337")
      (value "BLUE")
      (footprint "eagle-import:LED-0603")
      (libsource (lib "eagle-import") (part "SparkFun-LED_LED0603"))
    )
    (comp (ref "D338")
      (value "BLUE")
      (footprint "eagle-import:LED-0603")
      (libsource (lib "eagle-import") (part "SparkFun-LED_LED0603"))
    )
    (comp (ref "D339")
      (value "BLUE")
      (footprint "eagle-import:LED-0603")
      (libsource (lib "eagle-import") (part "SparkFun-LED_LED0603"))
    )
    (comp (ref "D340")
      (value "BLUE")
      (footprint "eagle-import:LED-0603")
      (libsource (lib "eagle-import") (part "SparkFun-LED_LED0603"))
    )
    (comp (ref "D341")
      (value "BLUE")
      (footprint "eagle-import:LED-0603")
      (libsource (lib "eagle-import") (part "SparkFun-LED_LED0603"))
    )
    (comp (ref "D342")
      (value "BLUE")
      (footprint "eagle-import:LED-0603")
      (libsource (lib "eagle-import") (part "SparkFun-LED_LED0603"))
    )
    (comp (ref "D343")
      (value "BLUE")
      (footprint "eagle-import:LED-0603")
      (libsource (lib "eagle-import") (part "SparkFun-LED_LED0603"))
    )
    (comp (ref "D344")
      (value "BLUE")
      (footprint "eagle-import:LED-0603")
      (libsource (lib "eagle-import") (part "SparkFun-LED_LED0603"))
    )
    (comp (ref "D345")
      (value "BLUE")
      (footprint "eagle-import:LED-0603")
      (libsource (lib "eagle-import") (part "SparkFun-LED_LED0603"))
    )
    (comp (ref "D346")
      (value "BLUE")
      (footprint "eagle-import:LED-0603")
      (libsource (lib "eagle-import") (part "SparkFun-LED_LED0603"))
    )
    (comp (ref "D347")
      (value "BLUE")
      (footprint "eagle-import:LED-0603")
      (libsource (lib "eagle-import") (part "SparkFun-LED_LED0603"))
    )
    (comp (ref "D348")
      (value "BLUE")
      (footprint "eagle-import:LED-0603")
      (libsource (lib "eagle-import") (part "SparkFun-LED_LED0603"))
    )
    (comp (ref "D349")
      (value "BLUE")
      (footprint "eagle-import:LED-0603")
      (libsource (lib "eagle-import") (part "SparkFun-LED_LED0603"))
    )
    (comp (ref "D350")
      (value "BLUE")
      (footprint "eagle-import:LED-0603")
      (libsource (lib "eagle-import") (part "SparkFun-LED_LED0603"))
    )
    (comp (ref "D351")
      (value "BLUE")
      (footprint "eagle-import:LED-0603")
      (libsource (lib "eagle-import") (part "SparkFun-LED_LED0603"))
    )
    (comp (ref "D352")
      (value "BLUE")
      (footprint "eagle-import:LED-0603")
      (libsource (lib "eagle-import") (part "SparkFun-LED_LED0603"))
    )
    (comp (ref "D353")
      (value "BLUE")
      (footprint "eagle-import:LED-0603")
      (libsource (lib "eagle-import") (part "SparkFun-LED_LED0603"))
    )
    (comp (ref "D354")
      (value "BLUE")
      (footprint "eagle-import:LED-0603")
      (libsource (lib "eagle-import") (part "SparkFun-LED_LED0603"))
    )
    (comp (ref "D355")
      (value "BLUE")
      (footprint "eagle-import:LED-0603")
      (libsource (lib "eagle-import") (part "SparkFun-LED_LED0603"))
    )
    (comp (ref "D356")
      (value "BLUE")
      (footprint "eagle-import:LED-0603")
      (libsource (lib "eagle-import") (part "SparkFun-LED_LED0603"))
    )
    (comp (ref "D357")
      (value "BLUE")
      (footprint "eagle-import:LED-0603")
      (libsource (lib "eagle-import") (part "SparkFun-LED_LED0603"))
    )
    (comp (ref "D358")
      (value "BLUE")
      (footprint "eagle-import:LED-0603")
      (libsource (lib "eagle-import") (part "SparkFun-LED_LED0603"))
    )
    (comp (ref "D359")
      (value "BLUE")
      (footprint "eagle-import:LED-0603")
      (libsource (lib "eagle-import") (part "SparkFun-LED_LED0603"))
    )
    (comp (ref "D501")
      (value "BLUE")
      (footprint "eagle-import:LED-0603")
      (libsource (lib "eagle-import") (part "LED0603"))
    )
    (comp (ref "D502")
      (value "RED")
      (footprint "eagle-import:LED-0603")
      (libsource (lib "eagle-import") (part "LED0603"))
    )
    (comp (ref "J001")
      (value "M04PTH")
      (footprint "eagle-import:1X04")
      (libsource (lib "eagle-import") (part "M04PTH"))
    )
    (comp (ref "J002")
      (value "M04PTH")
      (footprint "eagle-import:1X04")
      (libsource (lib "eagle-import") (part "M04PTH"))
    )
    (comp (ref "J003")
      (value "M06SIP")
      (footprint "eagle-import:1X06")
      (libsource (lib "eagle-import") (part "M06SIP"))
    )
    (comp (ref "J004")
      (value "M04PTH")
      (footprint "eagle-import:1X04")
      (libsource (lib "eagle-import") (part "M04PTH"))
    )
    (comp (ref "J005")
      (value "M06SIP")
      (footprint "eagle-import:1X06")
      (libsource (lib "eagle-import") (part "M06SIP"))
    )
    (comp (ref "J405")
      (value "M081X08")
      (footprint "eagle-import:1X08")
      (libsource (lib "eagle-import") (part "M081X08"))
    )
    (comp (ref "J406")
      (value "M081X08")
      (footprint "eagle-import:1X08")
      (libsource (lib "eagle-import") (part "M081X08"))
    )
    (comp (ref "JP1")
      (value "STAND-OFF")
      (footprint "eagle-import:STAND-OFF")
      (libsource (lib "eagle-import") (part "STAND-OFF"))
    )
    (comp (ref "JP2")
      (value "STAND-OFF")
      (footprint "eagle-import:STAND-OFF")
      (libsource (lib "eagle-import") (part "STAND-OFF"))
    )
    (comp (ref "JP3")
      (value "STAND-OFF")
      (footprint "eagle-import:STAND-OFF")
      (libsource (lib "eagle-import") (part "STAND-OFF"))
    )
    (comp (ref "JP4")
      (value "STAND-OFF")
      (footprint "eagle-import:STAND-OFF")
      (libsource (lib "eagle-import") (part "STAND-OFF"))
    )
    (comp (ref "JP5")
      (value "M02PTH")
      (footprint "eagle-import:1X02")
      (libsource (lib "eagle-import") (part "M02PTH"))
    )
    (comp (ref "R1")
      (value "47")
      (footprint "eagle-import:CRA04")
      (fields (field (name "DIGIKEY") "CRA4S847CT-ND"))
      (libsource (lib "eagle-import") (part "RP404"))
    )
    (comp (ref "R2")
      (value "47")
      (footprint "eagle-import:CRA04")
      (fields (field (name "DIGIKEY") "CRA4S847CT-ND"))
      (libsource (lib "eagle-import") (part "RP404"))
    )
    (comp (ref "R3")
      (value "47")
      (footprint "eagle-import:CRA04")
      (fields (field (name "DIGIKEY") "CRA4S847CT-ND"))
      (libsource (lib "eagle-import") (part "RP404"))
    )
    (comp (ref "R4")
      (value "47")
      (footprint "eagle-import:CRA04")
      (fields (field (name "DIGIKEY") "CRA4S847CT-ND"))
      (libsource (lib "eagle-import") (part "RP404"))
    )
    (comp (ref "R501")
      (value "680")
      (footprint "eagle-import:0603-RES")
      (libsource (lib "eagle-import") (part "RESISTOR0603-RES"))
    )
    (comp (ref "R502")
      (value "680")
      (footprint "eagle-import:0603-RES")
      (libsource (lib "eagle-import") (part "RESISTOR0603-RES"))
    )
    (comp (ref "R606")
      (value "10k")
      (footprint "eagle-import:CRA04")
      (fields (field (name "DIGIKEY") "CRA4S810KCT-ND"))
      (libsource (lib "eagle-import") (part "RP404"))
    )
    (comp (ref "S429")
      (value "B3U-1100P")
      (footprint "eagle-import:B3U-1100P")
      (fields (field (name "DIGIKEY") "SW1021CT-ND"))
      (libsource (lib "eagle-import") (part "B3U-1100P"))
    )
    (comp (ref "U401")
      (value "ATMEGA328")
      (footprint "eagle-import:TQFP32-08")
      (libsource (lib "eagle-import") (part "ATMEGA168"))
    )
    (comp (ref "U501")
      (value "FT232RLSSOP")
      (footprint "eagle-import:SSOP28DB")
      (libsource (lib "eagle-import") (part "FT232RLSSOP"))
    )
    (comp (ref "U602")
      (value "ZF7")
      (footprint "eagle-import:SC-70-6")
      (libsource (lib "eagle-import") (part "NC7SZ157"))
    )
    (comp (ref "Y401")
      (value "16MHz")
      (footprint "eagle-import:CRYSTAL_SMD")
      (fields (field (name "DIGIKEY") "887-1319-1-ND"))
      (libsource (lib "eagle-import") (part "TSX-3225"))
    )
  )
  (nets
    (net (code "1") (name "/3V3") (class "Default")
      (node (ref "J004") (pin "4") (pinfunction "4_4") (pintype "passive"))
      (node (ref "JP5") (pin "1") (pinfunction "1_1") (pintype "passive"))
      (node (ref "U501") (pin "17") (pinfunction "3V3OUT_17") (pintype "output"))
    )
    (net (code "2") (name "/AT_RX") (class "Default")
      (node (ref "U401") (pin "30") (pinfunction "PD0(RXD)_30") (pintype "bidirectional"))
      (node (ref "U602") (pin "4") (pinfunction "OUT_4") (pintype "bidirectional"))
    )
    (net (code "3") (name "/AT_TX") (class "Default")
      (node (ref "J004") (pin "1") (pinfunction "1_1") (pintype "passive"))
      (node (ref "U401") (pin "31") (pinfunction "PD1(TXD)_31") (pintype "bidirectional"))
      (node (ref "U501") (pin "5") (pinfunction "RXD_5") (pintype "input"))
    )
    (net (code "4") (name "/D12") (class "Default")
      (node (ref "J003") (pin "5") (pinfunction "5_5") (pintype "passive"))
      (node (ref "J005") (pin "5") (pinfunction "5_5") (pintype "passive"))
      (node (ref "R606") (pin "8") (pinfunction "2_8") (pintype "passive"))
      (node (ref "U401") (pin "16") (pinfunction "PB4(MISO)_16") (pintype "bidirectional"))
      (node (ref "U602") (pin "6") (pinfunction "SEL_6") (pintype "bidirectional"))
    )
    (net (code "5") (name "/GPS_TX") (class "Default")
      (node (ref "J004") (pin "2") (pinfunction "2_2") (pintype "passive"))
      (node (ref "U602") (pin "3") (pinfunction "I0_3") (pintype "bidirectional"))
    )
    (net (code "6") (name "/P01") (class "Default")
      (node (ref "J003") (pin "6") (pinfunction "6_6") (pintype "passive"))
      (node (ref "J005") (pin "6") (pinfunction "6_6") (pintype "passive"))
      (node (ref "R1") (pin "1") (pinfunction "1_1") (pintype "passive"))
      (node (ref "U401") (pin "15") (pinfunction "PB3(MOSI/OC2)_15") (pintype "bidirectional"))
    )
    (net (code "7") (name "/P02") (class "Default")
      (node (ref "R1") (pin "2") (pinfunction "1_2") (pintype "passive"))
      (node (ref "U401") (pin "2") (pinfunction "PD4(XCK/T0)_2") (pintype "bidirectional"))
    )
    (net (code "8") (name "/P03") (class "Default")
      (node (ref "R1") (pin "3") (pinfunction "1_3") (pintype "passive"))
      (node (ref "U401") (pin "14") (pinfunction "PB2(SS/OC1B)_14") (pintype "bidirectional"))
    )
    (net (code "9") (name "/P04") (class "Default")
      (node (ref "R1") (pin "4") (pinfunction "1_4") (pintype "passive"))
      (node (ref "U401") (pin "13") (pinfunction "PB1(OC1A)_13") (pintype "bidirectional"))
    )
    (net (code "10") (name "/P05") (class "Default")
      (node (ref "R2") (pin "1") (pinfunction "1_1") (pintype "passive"))
      (node (ref "U401") (pin "12") (pinfunction "PB0(ICP)_12") (pintype "bidirectional"))
    )
    (net (code "11") (name "/P06") (class "Default")
      (node (ref "R2") (pin "2") (pinfunction "1_2") (pintype "passive"))
      (node (ref "U401") (pin "11") (pinfunction "PD7(AIN1)_11") (pintype "bidirectional"))
    )
    (net (code "12") (name "/P07") (class "Default")
      (node (ref "R2") (pin "3") (pinfunction "1_3") (pintype "passive"))
      (node (ref "U401") (pin "10") (pinfunction "PD6(AIN0)_10") (pintype "bidirectional"))
    )
    (net (code "13") (name "/P08") (class "Default")
      (node (ref "R2") (pin "4") (pinfunction "1_4") (pintype "passive"))
      (node (ref "U401") (pin "9") (pinfunction "PD5(T1)_9") (pintype "bidirectional"))
    )
    (net (code "14") (name "/P09") (class "Default")
      (node (ref "R3") (pin "1") (pinfunction "1_1") (pintype "passive"))
      (node (ref "U401") (pin "1") (pinfunction "PD3(INT1)_1") (pintype "bidirectional"))
    )
    (net (code "15") (name "/P10") (class "Default")
      (node (ref "R3") (pin "2") (pinfunction "1_2") (pintype "passive"))
      (node (ref "U401") (pin "28") (pinfunction "PC5(ADC5/SCL)_28") (pintype "bidirectional"))
    )
    (net (code "16") (name "/P11") (class "Default")
      (node (ref "R3") (pin "3") (pinfunction "1_3") (pintype "passive"))
      (node (ref "U401") (pin "27") (pinfunction "PC4(ADC4/SDA)_27") (pintype "bidirectional"))
    )
    (net (code "17") (name "/P12") (class "Default")
      (node (ref "R3") (pin "4") (pinfunction "1_4") (pintype "passive"))
      (node (ref "U401") (pin "26") (pinfunction "PC3(ADC3)_26") (pintype "bidirectional"))
    )
    (net (code "18") (name "/P13") (class "Default")
      (node (ref "R4") (pin "1") (pinfunction "1_1") (pintype "passive"))
      (node (ref "U401") (pin "25") (pinfunction "PC2(ADC2)_25") (pintype "bidirectional"))
    )
    (net (code "19") (name "/P14") (class "Default")
      (node (ref "R4") (pin "2") (pinfunction "1_2") (pintype "passive"))
      (node (ref "U401") (pin "24") (pinfunction "PC1(ADC1)_24") (pintype "bidirectional"))
    )
    (net (code "20") (name "/P15") (class "Default")
      (node (ref "R4") (pin "3") (pinfunction "1_3") (pintype "passive"))
      (node (ref "U401") (pin "23") (pinfunction "PC0(ADC0)_23") (pintype "bidirectional"))
    )
    (net (code "21") (name "/P16") (class "Default")
      (node (ref "J003") (pin "4") (pinfunction "4_4") (pintype "passive"))
      (node (ref "J005") (pin "4") (pinfunction "4_4") (pintype "passive"))
      (node (ref "R4") (pin "4") (pinfunction "1_4") (pintype "passive"))
      (node (ref "U401") (pin "17") (pinfunction "PB5(SCK)_17") (pintype "bidirectional"))
    )
    (net (code "22") (name "/PPS") (class "Default")
      (node (ref "JP5") (pin "2") (pinfunction "2_2") (pintype "passive"))
      (node (ref "U401") (pin "32") (pinfunction "PD2(INT0)_32") (pintype "bidirectional"))
    )
    (net (code "23") (name "/Q01") (class "Default")
      (node (ref "D000") (pin "C") (pinfunction "C_C") (pintype "passive"))
      (node (ref "D015") (pin "C") (pinfunction "C_C") (pintype "passive"))
      (node (ref "D029") (pin "C") (pinfunction "C_C") (pintype "passive"))
      (node (ref "D042") (pin "C") (pinfunction "C_C") (pintype "passive"))
      (node (ref "D054") (pin "C") (pinfunction "C_C") (pintype "passive"))
      (node (ref "D105") (pin "C") (pinfunction "C_C") (pintype "passive"))
      (node (ref "D115") (pin "C") (pinfunction "C_C") (pintype "passive"))
      (node (ref "D124") (pin "C") (pinfunction "C_C") (pintype "passive"))
      (node (ref "D132") (pin "C") (pinfunction "C_C") (pintype "passive"))
      (node (ref "D139") (pin "C") (pinfunction "C_C") (pintype "passive"))
      (node (ref "D145") (pin "C") (pinfunction "C_C") (pintype "passive"))
      (node (ref "D150") (pin "C") (pinfunction "C_C") (pintype "passive"))
      (node (ref "D154") (pin "C") (pinfunction "C_C") (pintype "passive"))
      (node (ref "D157") (pin "C") (pinfunction "C_C") (pintype "passive"))
      (node (ref "D159") (pin "C") (pinfunction "C_C") (pintype "passive"))
      (node (ref "J406") (pin "1") (pinfunction "1_1") (pintype "passive"))
      (node (ref "R1") (pin "8") (pinfunction "2_8") (pintype "passive"))
    )
    (net (code "24") (name "/Q02") (class "Default")
      (node (ref "D000") (pin "A") (pinfunction "A_A") (pintype "passive"))
      (node (ref "D001") (pin "C") (pinfunction "C_C") (pintype "passive"))
      (node (ref "D016") (pin "C") (pinfunction "C_C") (pintype "passive"))
      (node (ref "D030") (pin "C") (pinfunction "C_C") (pintype "passive"))
      (node (ref "D043") (pin "C") (pinfunction "C_C") (pintype "passive"))
      (node (ref "D055") (pin "C") (pinfunction "C_C") (pintype "passive"))
      (node (ref "D106") (pin "C") (pinfunction "C_C") (pintype "passive"))
      (node (ref "D116") (pin "C") (pinfunction "C_C") (pintype "passive"))
      (node (ref "D125") (pin "C") (pinfunction "C_C") (pintype "passive"))
      (node (ref "D133") (pin "C") (pinfunction "C_C") (pintype "passive"))
      (node (ref "D140") (pin "C") (pinfunction "C_C") (pintype "passive"))
      (node (ref "D146") (pin "C") (pinfunction "C_C") (pintype "passive"))
      (node (ref "D151") (pin "C") (pinfunction "C_C") (pintype "passive"))
      (node (ref "D155") (pin "C") (pinfunction "C_C") (pintype "passive"))
      (node (ref "D158") (pin "C") (pinfunction "C_C") (pintype "passive"))
      (node (ref "J406") (pin "2") (pinfunction "2_2") (pintype "passive"))
      (node (ref "R1") (pin "7") (pinfunction "2_7") (pintype "passive"))
    )
    (net (code "25") (name "/Q03") (class "Default")
      (node (ref "D001") (pin "A") (pinfunction "A_A") (pintype "passive"))
      (node (ref "D002") (pin "C") (pinfunction "C_C") (pintype "passive"))
      (node (ref "D015") (pin "A") (pinfunction "A_A") (pintype "passive"))
      (node (ref "D017") (pin "C") (pinfunction "C_C") (pintype "passive"))
      (node (ref "D031") (pin "C") (pinfunction "C_C") (pintype "passive"))
      (node (ref "D044") (pin "C") (pinfunction "C_C") (pintype "passive"))
      (node (ref "D056") (pin "C") (pinfunction "C_C") (pintype "passive"))
      (node (ref "D107") (pin "C") (pinfunction "C_C") (pintype "passive"))
      (node (ref "D117") (pin "C") (pinfunction "C_C") (pintype "passive"))
      (node (ref "D126") (pin "C") (pinfunction "C_C") (pintype "passive"))
      (node (ref "D134") (pin "C") (pinfunction "C_C") (pintype "passive"))
      (node (ref "D141") (pin "C") (pinfunction "C_C") (pintype "passive"))
      (node (ref "D147") (pin "C") (pinfunction "C_C") (pintype "passive"))
      (node (ref "D152") (pin "C") (pinfunction "C_C") (pintype "passive"))
      (node (ref "D156") (pin "C") (pinfunction "C_C") (pintype "passive"))
      (node (ref "J406") (pin "3") (pinfunction "3_3") (pintype "passive"))
      (node (ref "R1") (pin "6") (pinfunction "2_6") (pintype "passive"))
    )
    (net (code "26") (name "/Q04") (class "Default")
      (node (ref "D002") (pin "A") (pinfunction "A_A") (pintype "passive"))
      (node (ref "D003") (pin "C") (pinfunction "C_C") (pintype "passive"))
      (node (ref "D016") (pin "A") (pinfunction "A_A") (pintype "passive"))
      (node (ref "D018") (pin "C") (pinfunction "C_C") (pintype "passive"))
      (node (ref "D029") (pin "A") (pinfunction "A_A") (pintype "passive"))
      (node (ref "D032") (pin "C") (pinfunction "C_C") (pintype "passive"))
      (node (ref "D045") (pin "C") (pinfunction "C_C") (pintype "passive"))
      (node (ref "D057") (pin "C") (pinfunction "C_C") (pintype "passive"))
      (node (ref "D108") (pin "C") (pinfunction "C_C") (pintype "passive"))
      (node (ref "D118") (pin "C") (pinfunction "C_C") (pintype "passive"))
      (node (ref "D127") (pin "C") (pinfunction "C_C") (pintype "passive"))
      (node (ref "D135") (pin "C") (pinfunction "C_C") (pintype "passive"))
      (node (ref "D142") (pin "C") (pinfunction "C_C") (pintype "passive"))
      (node (ref "D148") (pin "C") (pinfunction "C_C") (pintype "passive"))
      (node (ref "D153") (pin "C") (pinfunction "C_C") (pintype "passive"))
      (node (ref "J406") (pin "4") (pinfunction "4_4") (pintype "passive"))
      (node (ref "R1") (pin "5") (pinfunction "2_5") (pintype "passive"))
    )
    (net (code "27") (name "/Q05") (class "Default")
      (node (ref "D003") (pin "A") (pinfunction "A_A") (pintype "passive"))
      (node (ref "D004") (pin "C") (pinfunction "C_C") (pintype "passive"))
      (node (ref "D017") (pin "A") (pinfunction "A_A") (pintype "passive"))
      (node (ref "D019") (pin "C") (pinfunction "C_C") (pintype "passive"))
      (node (ref "D030") (pin "A") (pinfunction "A_A") (pintype "passive"))
      (node (ref "D033") (pin "C") (pinfunction "C_C") (pintype "passive"))
      (node (ref "D042") (pin "A") (pinfunction "A_A") (pintype "passive"))
      (node (ref "D046") (pin "C") (pinfunction "C_C") (pintype "passive"))
      (node (ref "D058") (pin "C") (pinfunction "C_C") (pintype "passive"))
      (node (ref "D109") (pin "C") (pinfunction "C_C") (pintype "passive"))
      (node (ref "D119") (pin "C") (pinfunction "C_C") (pintype "passive"))
      (node (ref "D128") (pin "C") (pinfunction "C_C") (pintype "passive"))
      (node (ref "D136") (pin "C") (pinfunction "C_C") (pintype "passive"))
      (node (ref "D143") (pin "C") (pinfunction "C_C") (pintype "passive"))
      (node (ref "D149") (pin "C") (pinfunction "C_C") (pintype "passive"))
      (node (ref "J406") (pin "5") (pinfunction "5_5") (pintype "passive"))
      (node (ref "R2") (pin "8") (pinfunction "2_8") (pintype "passive"))
    )
    (net (code "28") (name "/Q06") (class "Default")
      (node (ref "D004") (pin "A") (pinfunction "A_A") (pintype "passive"))
      (node (ref "D005") (pin "C") (pinfunction "C_C") (pintype "passive"))
      (node (ref "D018") (pin "A") (pinfunction "A_A") (pintype "passive"))
      (node (ref "D020") (pin "C") (pinfunction "C_C") (pintype "passive"))
      (node (ref "D031") (pin "A") (pinfunction "A_A") (pintype "passive"))
      (node (ref "D034") (pin "C") (pinfunction "C_C") (pintype "passive"))
      (node (ref "D043") (pin "A") (pinfunction "A_A") (pintype "passive"))
      (node (ref "D047") (pin "C") (pinfunction "C_C") (pintype "passive"))
      (node (ref "D054") (pin "A") (pinfunction "A_A") (pintype "passive"))
      (node (ref "D059") (pin "C") (pinfunction "C_C") (pintype "passive"))
      (node (ref "D110") (pin "C") (pinfunction "C_C") (pintype "passive"))
      (node (ref "D120") (pin "C") (pinfunction "C_C") (pintype "passive"))
      (node (ref "D129") (pin "C") (pinfunction "C_C") (pintype "passive"))
      (node (ref "D137") (pin "C") (pinfunction "C_C") (pintype "passive"))
      (node (ref "D144") (pin "C") (pinfunction "C_C") (pintype "passive"))
      (node (ref "J406") (pin "6") (pinfunction "6_6") (pintype "passive"))
      (node (ref "R2") (pin "7") (pinfunction "2_7") (pintype "passive"))
    )
    (net (code "29") (name "/Q07") (class "Default")
      (node (ref "D005") (pin "A") (pinfunction "A_A") (pintype "passive"))
      (node (ref "D006") (pin "C") (pinfunction "C_C") (pintype "passive"))
      (node (ref "D019") (pin "A") (pinfunction "A_A") (pintype "passive"))
      (node (ref "D021") (pin "C") (pinfunction "C_C") (pintype "passive"))
      (node (ref "D032") (pin "A") (pinfunction "A_A") (pintype "passive"))
      (node (ref "D035") (pin "C") (pinfunction "C_C") (pintype "passive"))
      (node (ref "D044") (pin "A") (pinfunction "A_A") (pintype "passive"))
      (node (ref "D048") (pin "C") (pinfunction "C_C") (pintype "passive"))
      (node (ref "D055") (pin "A") (pinfunction "A_A") (pintype "passive"))
      (node (ref "D100") (pin "C") (pinfunction "C_C") (pintype "passive"))
      (node (ref "D105") (pin "A") (pinfunction "A_A") (pintype "passive"))
      (node (ref "D111") (pin "C") (pinfunction "C_C") (pintype "passive"))
      (node (ref "D121") (pin "C") (pinfunction "C_C") (pintype "passive"))
      (node (ref "D130") (pin "C") (pinfunction "C_C") (pintype "passive"))
      (node (ref "D138") (pin "C") (pinfunction "C_C") (pintype "passive"))
      (node (ref "J406") (pin "7") (pinfunction "7_7") (pintype "passive"))
      (node (ref "R2") (pin "6") (pinfunction "2_6") (pintype "passive"))
    )
    (net (code "30") (name "/Q08") (class "Default")
      (node (ref "D006") (pin "A") (pinfunction "A_A") (pintype "passive"))
      (node (ref "D007") (pin "C") (pinfunction "C_C") (pintype "passive"))
      (node (ref "D020") (pin "A") (pinfunction "A_A") (pintype "passive"))
      (node (ref "D022") (pin "C") (pinfunction "C_C") (pintype "passive"))
      (node (ref "D033") (pin "A") (pinfunction "A_A") (pintype "passive"))
      (node (ref "D036") (pin "C") (pinfunction "C_C") (pintype "passive"))
      (node (ref "D045") (pin "A") (pinfunction "A_A") (pintype "passive"))
      (node (ref "D049") (pin "C") (pinfunction "C_C") (pintype "passive"))
      (node (ref "D056") (pin "A") (pinfunction "A_A") (pintype "passive"))
      (node (ref "D101") (pin "C") (pinfunction "C_C") (pintype "passive"))
      (node (ref "D106") (pin "A") (pinfunction "A_A") (pintype "passive"))
      (node (ref "D112") (pin "C") (pinfunction "C_C") (pintype "passive"))
      (node (ref "D115") (pin "A") (pinfunction "A_A") (pintype "passive"))
      (node (ref "D122") (pin "C") (pinfunction "C_C") (pintype "passive"))
      (node (ref "D131") (pin "C") (pinfunction "C_C") (pintype "passive"))
      (node (ref "J406") (pin "8") (pinfunction "8_8") (pintype "passive"))
      (node (ref "R2") (pin "5") (pinfunction "2_5") (pintype "passive"))
    )
    (net (code "31") (name "/Q09") (class "Default")
      (node (ref "D007") (pin "A") (pinfunction "A_A") (pintype "passive"))
      (node (ref "D008") (pin "C") (pinfunction "C_C") (pintype "passive"))
      (node (ref "D021") (pin "A") (pinfunction "A_A") (pintype "passive"))
      (node (ref "D023") (pin "C") (pinfunction "C_C") (pintype "passive"))
      (node (ref "D034") (pin "A") (pinfunction "A_A") (pintype "passive"))
      (node (ref "D037") (pin "C") (pinfunction "C_C") (pintype "passive"))
      (node (ref "D046") (pin "A") (pinfunction "A_A") (pintype "passive"))
      (node (ref "D050") (pin "C") (pinfunction "C_C") (pintype "passive"))
      (node (ref "D057") (pin "A") (pinfunction "A_A") (pintype "passive"))
      (node (ref "D102") (pin "C") (pinfunction "C_C") (pintype "passive"))
      (node (ref "D107") (pin "A") (pinfunction "A_A") (pintype "passive"))
      (node (ref "D113") (pin "C") (pinfunction "C_C") (pintype "passive"))
      (node (ref "D116") (pin "A") (pinfunction "A_A") (pintype "passive"))
      (node (ref "D123") (pin "C") (pinfunction "C_C") (pintype "passive"))
      (node (ref "D124") (pin "A") (pinfunction "A_A") (pintype "passive"))
      (node (ref "J405") (pin "1") (pinfunction "1_1") (pintype "passive"))
      (node (ref "R3") (pin "8") (pinfunction "2_8") (pintype "passive"))
    )
    (net (code "32") (name "/Q10") (class "Default")
      (node (ref "D008") (pin "A") (pinfunction "A_A") (pintype "passive"))
      (node (ref "D009") (pin "C") (pinfunction "C_C") (pintype "passive"))
      (node (ref "D022") (pin "A") (pinfunction "A_A") (pintype "passive"))
      (node (ref "D024") (pin "C") (pinfunction "C_C") (pintype "passive"))
      (node (ref "D035") (pin "A") (pinfunction "A_A") (pintype "passive"))
      (node (ref "D038") (pin "C") (pinfunction "C_C") (pintype "passive"))
      (node (ref "D047") (pin "A") (pinfunction "A_A") (pintype "passive"))
      (node (ref "D051") (pin "C") (pinfunction "C_C") (pintype "passive"))
      (node (ref "D058") (pin "A") (pinfunction "A_A") (pintype "passive"))
      (node (ref "D103") (pin "C") (pinfunction "C_C") (pintype "passive"))
      (node (ref "D108") (pin "A") (pinfunction "A_A") (pintype "passive"))
      (node (ref "D114") (pin "C") (pinfunction "C_C") (pintype "passive"))
      (node (ref "D117") (pin "A") (pinfunction "A_A") (pintype "passive"))
      (node (ref "D125") (pin "A") (pinfunction "A_A") (pintype "passive"))
      (node (ref "D132") (pin "A") (pinfunction "A_A") (pintype "passive"))
      (node (ref "J405") (pin "2") (pinfunction "2_2") (pintype "passive"))
      (node (ref "R3") (pin "7") (pinfunction "2_7") (pintype "passive"))
    )
    (net (code "33") (name "/Q11") (class "Default")
      (node (ref "D009") (pin "A") (pinfunction "A_A") (pintype "passive"))
      (node (ref "D010") (pin "C") (pinfunction "C_C") (pintype "passive"))
      (node (ref "D023") (pin "A") (pinfunction "A_A") (pintype "passive"))
      (node (ref "D025") (pin "C") (pinfunction "C_C") (pintype "passive"))
      (node (ref "D036") (pin "A") (pinfunction "A_A") (pintype "passive"))
      (node (ref "D039") (pin "C") (pinfunction "C_C") (pintype "passive"))
      (node (ref "D048") (pin "A") (pinfunction "A_A") (pintype "passive"))
      (node (ref "D052") (pin "C") (pinfunction "C_C") (pintype "passive"))
      (node (ref "D059") (pin "A") (pinfunction "A_A") (pintype "passive"))
      (node (ref "D104") (pin "C") (pinfunction "C_C") (pintype "passive"))
      (node (ref "D109") (pin "A") (pinfunction "A_A") (pintype "passive"))
      (node (ref "D118") (pin "A") (pinfunction "A_A") (pintype "passive"))
      (node (ref "D126") (pin "A") (pinfunction "A_A") (pintype "passive"))
      (node (ref "D133") (pin "A") (pinfunction "A_A") (pintype "passive"))
      (node (ref "D139") (pin "A") (pinfunction "A_A") (pintype "passive"))
      (node (ref "J405") (pin "3") (pinfunction "3_3") (pintype "passive"))
      (node (ref "R3") (pin "6") (pinfunction "2_6") (pintype "passive"))
    )
    (net (code "34") (name "/Q12") (class "Default")
      (node (ref "D010") (pin "A") (pinfunction "A_A") (pintype "passive"))
      (node (ref "D011") (pin "C") (pinfunction "C_C") (pintype "passive"))
      (node (ref "D024") (pin "A") (pinfunction "A_A") (pintype "passive"))
      (node (ref "D026") (pin "C") (pinfunction "C_C") (pintype "passive"))
      (node (ref "D037") (pin "A") (pinfunction "A_A") (pintype "passive"))
      (node (ref "D040") (pin "C") (pinfunction "C_C") (pintype "passive"))
      (node (ref "D049") (pin "A") (pinfunction "A_A") (pintype "passive"))
      (node (ref "D053") (pin "C") (pinfunction "C_C") (pintype "passive"))
      (node (ref "D100") (pin "A") (pinfunction "A_A") (pintype "passive"))
      (node (ref "D110") (pin "A") (pinfunction "A_A") (pintype "passive"))
      (node (ref "D119") (pin "A") (pinfunction "A_A") (pintype "passive"))
      (node (ref "D127") (pin "A") (pinfunction "A_A") (pintype "passive"))
      (node (ref "D134") (pin "A") (pinfunction "A_A") (pintype "passive"))
      (node (ref "D140") (pin "A") (pinfunction "A_A") (pintype "passive"))
      (node (ref "D145") (pin "A") (pinfunction "A_A") (pintype "passive"))
      (node (ref "J405") (pin "4") (pinfunction "4_4") (pintype "passive"))
      (node (ref "R3") (pin "5") (pinfunction "2_5") (pintype "passive"))
    )
    (net (code "35") (name "/Q13") (class "Default")
      (node (ref "D011") (pin "A") (pinfunction "A_A") (pintype "passive"))
      (node (ref "D012") (pin "C") (pinfunction "C_C") (pintype "passive"))
      (node (ref "D025") (pin "A") (pinfunction "A_A") (pintype "passive"))
      (node (ref "D027") (pin "C") (pinfunction "C_C") (pintype "passive"))
      (node (ref "D038") (pin "A") (pinfunction "A_A") (pintype "passive"))
      (node (ref "D041") (pin "C") (pinfunction "C_C") (pintype "passive"))
      (node (ref "D050") (pin "A") (pinfunction "A_A") (pintype "passive"))
      (node (ref "D101") (pin "A") (pinfunction "A_A") (pintype "passive"))
      (node (ref "D111") (pin "A") (pinfunction "A_A") (pintype "passive"))
      (node (ref "D120") (pin "A") (pinfunction "A_A") (pintype "passive"))
      (node (ref "D128") (pin "A") (pinfunction "A_A") (pintype "passive"))
      (node (ref "D135") (pin "A") (pinfunction "A_A") (pintype "passive"))
      (node (ref "D141") (pin "A") (pinfunction "A_A") (pintype "passive"))
      (node (ref "D146") (pin "A") (pinfunction "A_A") (pintype "passive"))
      (node (ref "D150") (pin "A") (pinfunction "A_A") (pintype "passive"))
      (node (ref "J405") (pin "5") (pinfunction "5_5") (pintype "passive"))
      (node (ref "R4") (pin "8") (pinfunction "2_8") (pintype "passive"))
    )
    (net (code "36") (name "/Q14") (class "Default")
      (node (ref "D012") (pin "A") (pinfunction "A_A") (pintype "passive"))
      (node (ref "D013") (pin "C") (pinfunction "C_C") (pintype "passive"))
      (node (ref "D026") (pin "A") (pinfunction "A_A") (pintype "passive"))
      (node (ref "D028") (pin "C") (pinfunction "C_C") (pintype "passive"))
      (node (ref "D039") (pin "A") (pinfunction "A_A") (pintype "passive"))
      (node (ref "D051") (pin "A") (pinfunction "A_A") (pintype "passive"))
      (node (ref "D102") (pin "A") (pinfunction "A_A") (pintype "passive"))
      (node (ref "D112") (pin "A") (pinfunction "A_A") (pintype "passive"))
      (node (ref "D121") (pin "A") (pinfunction "A_A") (pintype "passive"))
      (node (ref "D129") (pin "A") (pinfunction "A_A") (pintype "passive"))
      (node (ref "D136") (pin "A") (pinfunction "A_A") (pintype "passive"))
      (node (ref "D142") (pin "A") (pinfunction "A_A") (pintype "passive"))
      (node (ref "D147") (pin "A") (pinfunction "A_A") (pintype "passive"))
      (node (ref "D151") (pin "A") (pinfunction "A_A") (pintype "passive"))
      (node (ref "D154") (pin "A") (pinfunction "A_A") (pintype "passive"))
      (node (ref "J405") (pin "6") (pinfunction "6_6") (pintype "passive"))
      (node (ref "R4") (pin "7") (pinfunction "2_7") (pintype "passive"))
    )
    (net (code "37") (name "/Q15") (class "Default")
      (node (ref "D013") (pin "A") (pinfunction "A_A") (pintype "passive"))
      (node (ref "D014") (pin "C") (pinfunction "C_C") (pintype "passive"))
      (node (ref "D027") (pin "A") (pinfunction "A_A") (pintype "passive"))
      (node (ref "D040") (pin "A") (pinfunction "A_A") (pintype "passive"))
      (node (ref "D052") (pin "A") (pinfunction "A_A") (pintype "passive"))
      (node (ref "D103") (pin "A") (pinfunction "A_A") (pintype "passive"))
      (node (ref "D113") (pin "A") (pinfunction "A_A") (pintype "passive"))
      (node (ref "D122") (pin "A") (pinfunction "A_A") (pintype "passive"))
      (node (ref "D130") (pin "A") (pinfunction "A_A") (pintype "passive"))
      (node (ref "D137") (pin "A") (pinfunction "A_A") (pintype "passive"))
      (node (ref "D143") (pin "A") (pinfunction "A_A") (pintype "passive"))
      (node (ref "D148") (pin "A") (pinfunction "A_A") (pintype "passive"))
      (node (ref "D152") (pin "A") (pinfunction "A_A") (pintype "passive"))
      (node (ref "D155") (pin "A") (pinfunction "A_A") (pintype "passive"))
      (node (ref "D157") (pin "A") (pinfunction "A_A") (pintype "passive"))
      (node (ref "J405") (pin "7") (pinfunction "7_7") (pintype "passive"))
      (node (ref "R4") (pin "6") (pinfunction "2_6") (pintype "passive"))
    )
    (net (code "38") (name "/Q16") (class "Default")
      (node (ref "D014") (pin "A") (pinfunction "A_A") (pintype "passive"))
      (node (ref "D028") (pin "A") (pinfunction "A_A") (pintype "passive"))
      (node (ref "D041") (pin "A") (pinfunction "A_A") (pintype "passive"))
      (node (ref "D053") (pin "A") (pinfunction "A_A") (pintype "passive"))
      (node (ref "D104") (pin "A") (pinfunction "A_A") (pintype "passive"))
      (node (ref "D114") (pin "A") (pinfunction "A_A") (pintype "passive"))
      (node (ref "D123") (pin "A") (pinfunction "A_A") (pintype "passive"))
      (node (ref "D131") (pin "A") (pinfunction "A_A") (pintype "passive"))
      (node (ref "D138") (pin "A") (pinfunction "A_A") (pintype "passive"))
      (node (ref "D144") (pin "A") (pinfunction "A_A") (pintype "passive"))
      (node (ref "D149") (pin "A") (pinfunction "A_A") (pintype "passive"))
      (node (ref "D153") (pin "A") (pinfunction "A_A") (pintype "passive"))
      (node (ref "D156") (pin "A") (pinfunction "A_A") (pintype "passive"))
      (node (ref "D158") (pin "A") (pinfunction "A_A") (pintype "passive"))
      (node (ref "D159") (pin "A") (pinfunction "A_A") (pintype "passive"))
      (node (ref "J405") (pin "8") (pinfunction "8_8") (pintype "passive"))
      (node (ref "R4") (pin "5") (pinfunction "2_5") (pintype "passive"))
    )
    (net (code "39") (name "/RESET") (class "Default")
      (node (ref "C502") (pin "1") (pinfunction "1_1") (pintype "passive"))
      (node (ref "J003") (pin "1") (pinfunction "1_1") (pintype "passive"))
      (node (ref "J005") (pin "1") (pinfunction "1_1") (pintype "passive"))
      (node (ref "R606") (pin "5") (pinfunction "2_5") (pintype "passive"))
      (node (ref "S429") (pin "P$2") (pinfunction "2_P$2") (pintype "bidirectional"))
      (node (ref "U401") (pin "29") (pinfunction "PC6(/RESET)_29") (pintype "bidirectional"))
    )
    (net (code "40") (name "/USBD+") (class "Default")
      (node (ref "J001") (pin "1") (pinfunction "1_1") (pintype "passive"))
      (node (ref "J002") (pin "1") (pinfunction "1_1") (pintype "passive"))
      (node (ref "U501") (pin "15") (pinfunction "USBDP_15") (pintype "bidirectional"))
    )
    (net (code "41") (name "/USBD-") (class "Default")
      (node (ref "J001") (pin "2") (pinfunction "2_2") (pintype "passive"))
      (node (ref "J002") (pin "2") (pinfunction "2_2") (pintype "passive"))
      (node (ref "U501") (pin "16") (pinfunction "USBDM_16") (pintype "bidirectional"))
    )
    (net (code "42") (name "/USB_TX") (class "Default")
      (node (ref "U501") (pin "1") (pinfunction "TXD_1") (pintype "output"))
      (node (ref "U602") (pin "1") (pinfunction "I1_1") (pintype "bidirectional"))
    )
    (net (code "43") (name "/XTAL1") (class "Default")
      (node (ref "C407") (pin "2") (pinfunction "2_2") (pintype "passive"))
      (node (ref "U401") (pin "7") (pinfunction "PB6(XTAL1/TOSC1)_7") (pintype "bidirectional"))
      (node (ref "Y401") (pin "1") (pinfunction "1_1") (pintype "bidirectional"))
    )
    (net (code "44") (name "/XTAL2") (class "Default")
      (node (ref "C408") (pin "2") (pinfunction "2_2") (pintype "passive"))
      (node (ref "U401") (pin "8") (pinfunction "PB7(XTAL2/TOSC2)_8") (pintype "bidirectional"))
      (node (ref "Y401") (pin "3") (pinfunction "2_3") (pintype "bidirectional"))
    )
    (net (code "45") (name "GND") (class "Default")
      (node (ref "C010") (pin "2") (pinfunction "2_2") (pintype "passive"))
      (node (ref "C407") (pin "1") (pinfunction "1_1") (pintype "passive"))
      (node (ref "C408") (pin "1") (pinfunction "1_1") (pintype "passive"))
      (node (ref "C418") (pin "1") (pinfunction "1_1") (pintype "passive"))
      (node (ref "C420") (pin "2") (pinfunction "2_2") (pintype "passive"))
      (node (ref "J001") (pin "4") (pinfunction "4_4") (pintype "passive"))
      (node (ref "J002") (pin "4") (pinfunction "4_4") (pintype "passive"))
      (node (ref "J003") (pin "3") (pinfunction "3_3") (pintype "passive"))
      (node (ref "J004") (pin "3") (pinfunction "3_3") (pintype "passive"))
      (node (ref "J005") (pin "3") (pinfunction "3_3") (pintype "passive"))
      (node (ref "S429") (pin "P$1") (pinfunction "1_P$1") (pintype "bidirectional"))
      (node (ref "S429") (pin "P$3") (pinfunction "1_P$3") (pintype "bidirectional"))
      (node (ref "U401") (pin "21") (pinfunction "GND_21") (pintype "bidirectional"))
      (node (ref "U401") (pin "3") (pinfunction "GND_3") (pintype "bidirectional"))
      (node (ref "U401") (pin "5") (pinfunction "AGND_5") (pintype "bidirectional"))
      (node (ref "U501") (pin "18") (pinfunction "GND18_18") (pintype "power_in"))
      (node (ref "U501") (pin "21") (pinfunction "GND21_21") (pintype "power_in"))
      (node (ref "U501") (pin "25") (pinfunction "AGND_25") (pintype "power_in"))
      (node (ref "U501") (pin "26") (pinfunction "TEST_26") (pintype "input"))
      (node (ref "U501") (pin "7") (pinfunction "GND7_7") (pintype "power_in"))
      (node (ref "U602") (pin "2") (pinfunction "GND_2") (pintype "bidirectional"))
      (node (ref "Y401") (pin "2") (pinfunction "1_2") (pintype "bidirectional"))
      (node (ref "Y401") (pin "4") (pinfunction "1_4") (pintype "bidirectional"))
    )
    (net (code "46") (name "Net-(D501-PadC)") (class "Default")
      (node (ref "D501") (pin "C") (pinfunction "C_C") (pintype "passive"))
      (node (ref "R501") (pin "2") (pinfunction "2_2") (pintype "passive"))
    )
    (net (code "47") (name "Net-(D502-PadC)") (class "Default")
      (node (ref "D502") (pin "C") (pinfunction "C_C") (pintype "passive"))
      (node (ref "R502") (pin "2") (pinfunction "2_2") (pintype "passive"))
    )
    (net (code "48") (name "Net-(U401-AREF)") (class "Default")
      (node (ref "C420") (pin "1") (pinfunction "1_1") (pintype "passive"))
      (node (ref "U401") (pin "20") (pinfunction "AREF_20") (pintype "bidirectional"))
    )
    (net (code "49") (name "Net-(U501-DTR)") (class "Default")
      (node (ref "C502") (pin "2") (pinfunction "2_2") (pintype "passive"))
      (node (ref "U501") (pin "2") (pinfunction "DTR_2") (pintype "output"))
    )
    (net (code "50") (name "Net-(U501-RXLED)") (class "Default")
      (node (ref "R502") (pin "1") (pinfunction "1_1") (pintype "passive"))
      (node (ref "U501") (pin "22") (pinfunction "RXLED_22") (pintype "input"))
    )
    (net (code "51") (name "Net-(U501-TXLED)") (class "Default")
      (node (ref "R501") (pin "1") (pinfunction "1_1") (pintype "passive"))
      (node (ref "U501") (pin "23") (pinfunction "TXLED_23") (pintype "input"))
    )
    (net (code "52") (name "VCC") (class "Default")
      (node (ref "C010") (pin "1") (pinfunction "1_1") (pintype "passive"))
      (node (ref "C418") (pin "2") (pinfunction "2_2") (pintype "passive"))
      (node (ref "D501") (pin "A") (pinfunction "A_A") (pintype "passive"))
      (node (ref "D502") (pin "A") (pinfunction "A_A") (pintype "passive"))
      (node (ref "J001") (pin "3") (pinfunction "3_3") (pintype "passive"))
      (node (ref "J002") (pin "3") (pinfunction "3_3") (pintype "passive"))
      (node (ref "J003") (pin "2") (pinfunction "2_2") (pintype "passive"))
      (node (ref "J005") (pin "2") (pinfunction "2_2") (pintype "passive"))
      (node (ref "R606") (pin "1") (pinfunction "1_1") (pintype "passive"))
      (node (ref "R606") (pin "4") (pinfunction "1_4") (pintype "passive"))
      (node (ref "U401") (pin "18") (pinfunction "AVCC_18") (pintype "bidirectional"))
      (node (ref "U401") (pin "4") (pinfunction "VCC_4") (pintype "bidirectional"))
      (node (ref "U401") (pin "6") (pinfunction "VCC_6") (pintype "bidirectional"))
      (node (ref "U501") (pin "20") (pinfunction "VCC_20") (pintype "power_in"))
      (node (ref "U501") (pin "4") (pinfunction "VCCIO_4") (pintype "power_in"))
      (node (ref "U602") (pin "5") (pinfunction "VCC_5") (pintype "bidirectional"))
    )
    (net (code "53") (name "unconnected-(D200-PadA)") (class "Default")
      (node (ref "D200") (pin "A") (pinfunction "A_A") (pintype "passive"))
    )
    (net (code "54") (name "unconnected-(D200-PadC)") (class "Default")
      (node (ref "D200") (pin "C") (pinfunction "C_C") (pintype "passive"))
    )
    (net (code "55") (name "unconnected-(D201-PadA)") (class "Default")
      (node (ref "D201") (pin "A") (pinfunction "A_A") (pintype "passive"))
    )
    (net (code "56") (name "unconnected-(D201-PadC)") (class "Default")
      (node (ref "D201") (pin "C") (pinfunction "C_C") (pintype "passive"))
    )
    (net (code "57") (name "unconnected-(D202-PadA)") (class "Default")
      (node (ref "D202") (pin "A") (pinfunction "A_A") (pintype "passive"))
    )
    (net (code "58") (name "unconnected-(D202-PadC)") (class "Default")
      (node (ref "D202") (pin "C") (pinfunction "C_C") (pintype "passive"))
    )
    (net (code "59") (name "unconnected-(D203-PadA)") (class "Default")
      (node (ref "D203") (pin "A") (pinfunction "A_A") (pintype "passive"))
    )
    (net (code "60") (name "unconnected-(D203-PadC)") (class "Default")
      (node (ref "D203") (pin "C") (pinfunction "C_C") (pintype "passive"))
    )
    (net (code "61") (name "unconnected-(D204-PadA)") (class "Default")
      (node (ref "D204") (pin "A") (pinfunction "A_A") (pintype "passive"))
    )
    (net (code "62") (name "unconnected-(D204-PadC)") (class "Default")
      (node (ref "D204") (pin "C") (pinfunction "C_C") (pintype "passive"))
    )
    (net (code "63") (name "unconnected-(D205-PadA)") (class "Default")
      (node (ref "D205") (pin "A") (pinfunction "A_A") (pintype "passive"))
    )
    (net (code "64") (name "unconnected-(D205-PadC)") (class "Default")
      (node (ref "D205") (pin "C") (pinfunction "C_C") (pintype "passive"))
    )
    (net (code "65") (name "unconnected-(D206-PadA)") (class "Default")
      (node (ref "D206") (pin "A") (pinfunction "A_A") (pintype "passive"))
    )
    (net (code "66") (name "unconnected-(D206-PadC)") (class "Default")
      (node (ref "D206") (pin "C") (pinfunction "C_C") (pintype "passive"))
    )
    (net (code "67") (name "unconnected-(D207-PadA)") (class "Default")
      (node (ref "D207") (pin "A") (pinfunction "A_A") (pintype "passive"))
    )
    (net (code "68") (name "unconnected-(D207-PadC)") (class "Default")
      (node (ref "D207") (pin "C") (pinfunction "C_C") (pintype "passive"))
    )
    (net (code "69") (name "unconnected-(D208-PadA)") (class "Default")
      (node (ref "D208") (pin "A") (pinfunction "A_A") (pintype "passive"))
    )
    (net (code "70") (name "unconnected-(D208-PadC)") (class "Default")
      (node (ref "D208") (pin "C") (pinfunction "C_C") (pintype "passive"))
    )
    (net (code "71") (name "unconnected-(D209-PadA)") (class "Default")
      (node (ref "D209") (pin "A") (pinfunction "A_A") (pintype "passive"))
    )
    (net (code "72") (name "unconnected-(D209-PadC)") (class "Default")
      (node (ref "D209") (pin "C") (pinfunction "C_C") (pintype "passive"))
    )
    (net (code "73") (name "unconnected-(D210-PadA)") (class "Default")
      (node (ref "D210") (pin "A") (pinfunction "A_A") (pintype "passive"))
    )
    (net (code "74") (name "unconnected-(D210-PadC)") (class "Default")
      (node (ref "D210") (pin "C") (pinfunction "C_C") (pintype "passive"))
    )
    (net (code "75") (name "unconnected-(D211-PadA)") (class "Default")
      (node (ref "D211") (pin "A") (pinfunction "A_A") (pintype "passive"))
    )
    (net (code "76") (name "unconnected-(D211-PadC)") (class "Default")
      (node (ref "D211") (pin "C") (pinfunction "C_C") (pintype "passive"))
    )
    (net (code "77") (name "unconnected-(D212-PadA)") (class "Default")
      (node (ref "D212") (pin "A") (pinfunction "A_A") (pintype "passive"))
    )
    (net (code "78") (name "unconnected-(D212-PadC)") (class "Default")
      (node (ref "D212") (pin "C") (pinfunction "C_C") (pintype "passive"))
    )
    (net (code "79") (name "unconnected-(D213-PadA)") (class "Default")
      (node (ref "D213") (pin "A") (pinfunction "A_A") (pintype "passive"))
    )
    (net (code "80") (name "unconnected-(D213-PadC)") (class "Default")
      (node (ref "D213") (pin "C") (pinfunction "C_C") (pintype "passive"))
    )
    (net (code "81") (name "unconnected-(D214-PadA)") (class "Default")
      (node (ref "D214") (pin "A") (pinfunction "A_A") (pintype "passive"))
    )
    (net (code "82") (name "unconnected-(D214-PadC)") (class "Default")
      (node (ref "D214") (pin "C") (pinfunction "C_C") (pintype "passive"))
    )
    (net (code "83") (name "unconnected-(D215-PadA)") (class "Default")
      (node (ref "D215") (pin "A") (pinfunction "A_A") (pintype "passive"))
    )
    (net (code "84") (name "unconnected-(D215-PadC)") (class "Default")
      (node (ref "D215") (pin "C") (pinfunction "C_C") (pintype "passive"))
    )
    (net (code "85") (name "unconnected-(D216-PadA)") (class "Default")
      (node (ref "D216") (pin "A") (pinfunction "A_A") (pintype "passive"))
    )
    (net (code "86") (name "unconnected-(D216-PadC)") (class "Default")
      (node (ref "D216") (pin "C") (pinfunction "C_C") (pintype "passive"))
    )
    (net (code "87") (name "unconnected-(D217-PadA)") (class "Default")
      (node (ref "D217") (pin "A") (pinfunction "A_A") (pintype "passive"))
    )
    (net (code "88") (name "unconnected-(D217-PadC)") (class "Default")
      (node (ref "D217") (pin "C") (pinfunction "C_C") (pintype "passive"))
    )
    (net (code "89") (name "unconnected-(D218-PadA)") (class "Default")
      (node (ref "D218") (pin "A") (pinfunction "A_A") (pintype "passive"))
    )
    (net (code "90") (name "unconnected-(D218-PadC)") (class "Default")
      (node (ref "D218") (pin "C") (pinfunction "C_C") (pintype "passive"))
    )
    (net (code "91") (name "unconnected-(D219-PadA)") (class "Default")
      (node (ref "D219") (pin "A") (pinfunction "A_A") (pintype "passive"))
    )
    (net (code "92") (name "unconnected-(D219-PadC)") (class "Default")
      (node (ref "D219") (pin "C") (pinfunction "C_C") (pintype "passive"))
    )
    (net (code "93") (name "unconnected-(D220-PadA)") (class "Default")
      (node (ref "D220") (pin "A") (pinfunction "A_A") (pintype "passive"))
    )
    (net (code "94") (name "unconnected-(D220-PadC)") (class "Default")
      (node (ref "D220") (pin "C") (pinfunction "C_C") (pintype "passive"))
    )
    (net (code "95") (name "unconnected-(D221-PadA)") (class "Default")
      (node (ref "D221") (pin "A") (pinfunction "A_A") (pintype "passive"))
    )
    (net (code "96") (name "unconnected-(D221-PadC)") (class "Default")
      (node (ref "D221") (pin "C") (pinfunction "C_C") (pintype "passive"))
    )
    (net (code "97") (name "unconnected-(D222-PadA)") (class "Default")
      (node (ref "D222") (pin "A") (pinfunction "A_A") (pintype "passive"))
    )
    (net (code "98") (name "unconnected-(D222-PadC)") (class "Default")
      (node (ref "D222") (pin "C") (pinfunction "C_C") (pintype "passive"))
    )
    (net (code "99") (name "unconnected-(D223-PadA)") (class "Default")
      (node (ref "D223") (pin "A") (pinfunction "A_A") (pintype "passive"))
    )
    (net (code "100") (name "unconnected-(D223-PadC)") (class "Default")
      (node (ref "D223") (pin "C") (pinfunction "C_C") (pintype "passive"))
    )
    (net (code "101") (name "unconnected-(D224-PadA)") (class "Default")
      (node (ref "D224") (pin "A") (pinfunction "A_A") (pintype "passive"))
    )
    (net (code "102") (name "unconnected-(D224-PadC)") (class "Default")
      (node (ref "D224") (pin "C") (pinfunction "C_C") (pintype "passive"))
    )
    (net (code "103") (name "unconnected-(D225-PadA)") (class "Default")
      (node (ref "D225") (pin "A") (pinfunction "A_A") (pintype "passive"))
    )
    (net (code "104") (name "unconnected-(D225-PadC)") (class "Default")
      (node (ref "D225") (pin "C") (pinfunction "C_C") (pintype "passive"))
    )
    (net (code "105") (name "unconnected-(D226-PadA)") (class "Default")
      (node (ref "D226") (pin "A") (pinfunction "A_A") (pintype "passive"))
    )
    (net (code "106") (name "unconnected-(D226-PadC)") (class "Default")
      (node (ref "D226") (pin "C") (pinfunction "C_C") (pintype "passive"))
    )
    (net (code "107") (name "unconnected-(D227-PadA)") (class "Default")
      (node (ref "D227") (pin "A") (pinfunction "A_A") (pintype "passive"))
    )
    (net (code "108") (name "unconnected-(D227-PadC)") (class "Default")
      (node (ref "D227") (pin "C") (pinfunction "C_C") (pintype "passive"))
    )
    (net (code "109") (name "unconnected-(D228-PadA)") (class "Default")
      (node (ref "D228") (pin "A") (pinfunction "A_A") (pintype "passive"))
    )
    (net (code "110") (name "unconnected-(D228-PadC)") (class "Default")
      (node (ref "D228") (pin "C") (pinfunction "C_C") (pintype "passive"))
    )
    (net (code "111") (name "unconnected-(D229-PadA)") (class "Default")
      (node (ref "D229") (pin "A") (pinfunction "A_A") (pintype "passive"))
    )
    (net (code "112") (name "unconnected-(D229-PadC)") (class "Default")
      (node (ref "D229") (pin "C") (pinfunction "C_C") (pintype "passive"))
    )
    (net (code "113") (name "unconnected-(D230-PadA)") (class "Default")
      (node (ref "D230") (pin "A") (pinfunction "A_A") (pintype "passive"))
    )
    (net (code "114") (name "unconnected-(D230-PadC)") (class "Default")
      (node (ref "D230") (pin "C") (pinfunction "C_C") (pintype "passive"))
    )
    (net (code "115") (name "unconnected-(D231-PadA)") (class "Default")
      (node (ref "D231") (pin "A") (pinfunction "A_A") (pintype "passive"))
    )
    (net (code "116") (name "unconnected-(D231-PadC)") (class "Default")
      (node (ref "D231") (pin "C") (pinfunction "C_C") (pintype "passive"))
    )
    (net (code "117") (name "unconnected-(D232-PadA)") (class "Default")
      (node (ref "D232") (pin "A") (pinfunction "A_A") (pintype "passive"))
    )
    (net (code "118") (name "unconnected-(D232-PadC)") (class "Default")
      (node (ref "D232") (pin "C") (pinfunction "C_C") (pintype "passive"))
    )
    (net (code "119") (name "unconnected-(D233-PadA)") (class "Default")
      (node (ref "D233") (pin "A") (pinfunction "A_A") (pintype "passive"))
    )
    (net (code "120") (name "unconnected-(D233-PadC)") (class "Default")
      (node (ref "D233") (pin "C") (pinfunction "C_C") (pintype "passive"))
    )
    (net (code "121") (name "unconnected-(D234-PadA)") (class "Default")
      (node (ref "D234") (pin "A") (pinfunction "A_A") (pintype "passive"))
    )
    (net (code "122") (name "unconnected-(D234-PadC)") (class "Default")
      (node (ref "D234") (pin "C") (pinfunction "C_C") (pintype "passive"))
    )
    (net (code "123") (name "unconnected-(D235-PadA)") (class "Default")
      (node (ref "D235") (pin "A") (pinfunction "A_A") (pintype "passive"))
    )
    (net (code "124") (name "unconnected-(D235-PadC)") (class "Default")
      (node (ref "D235") (pin "C") (pinfunction "C_C") (pintype "passive"))
    )
    (net (code "125") (name "unconnected-(D236-PadA)") (class "Default")
      (node (ref "D236") (pin "A") (pinfunction "A_A") (pintype "passive"))
    )
    (net (code "126") (name "unconnected-(D236-PadC)") (class "Default")
      (node (ref "D236") (pin "C") (pinfunction "C_C") (pintype "passive"))
    )
    (net (code "127") (name "unconnected-(D237-PadA)") (class "Default")
      (node (ref "D237") (pin "A") (pinfunction "A_A") (pintype "passive"))
    )
    (net (code "128") (name "unconnected-(D237-PadC)") (class "Default")
      (node (ref "D237") (pin "C") (pinfunction "C_C") (pintype "passive"))
    )
    (net (code "129") (name "unconnected-(D238-PadA)") (class "Default")
      (node (ref "D238") (pin "A") (pinfunction "A_A") (pintype "passive"))
    )
    (net (code "130") (name "unconnected-(D238-PadC)") (class "Default")
      (node (ref "D238") (pin "C") (pinfunction "C_C") (pintype "passive"))
    )
    (net (code "131") (name "unconnected-(D239-PadA)") (class "Default")
      (node (ref "D239") (pin "A") (pinfunction "A_A") (pintype "passive"))
    )
    (net (code "132") (name "unconnected-(D239-PadC)") (class "Default")
      (node (ref "D239") (pin "C") (pinfunction "C_C") (pintype "passive"))
    )
    (net (code "133") (name "unconnected-(D240-PadA)") (class "Default")
      (node (ref "D240") (pin "A") (pinfunction "A_A") (pintype "passive"))
    )
    (net (code "134") (name "unconnected-(D240-PadC)") (class "Default")
      (node (ref "D240") (pin "C") (pinfunction "C_C") (pintype "passive"))
    )
    (net (code "135") (name "unconnected-(D241-PadA)") (class "Default")
      (node (ref "D241") (pin "A") (pinfunction "A_A") (pintype "passive"))
    )
    (net (code "136") (name "unconnected-(D241-PadC)") (class "Default")
      (node (ref "D241") (pin "C") (pinfunction "C_C") (pintype "passive"))
    )
    (net (code "137") (name "unconnected-(D242-PadA)") (class "Default")
      (node (ref "D242") (pin "A") (pinfunction "A_A") (pintype "passive"))
    )
    (net (code "138") (name "unconnected-(D242-PadC)") (class "Default")
      (node (ref "D242") (pin "C") (pinfunction "C_C") (pintype "passive"))
    )
    (net (code "139") (name "unconnected-(D243-PadA)") (class "Default")
      (node (ref "D243") (pin "A") (pinfunction "A_A") (pintype "passive"))
    )
    (net (code "140") (name "unconnected-(D243-PadC)") (class "Default")
      (node (ref "D243") (pin "C") (pinfunction "C_C") (pintype "passive"))
    )
    (net (code "141") (name "unconnected-(D244-PadA)") (class "Default")
      (node (ref "D244") (pin "A") (pinfunction "A_A") (pintype "passive"))
    )
    (net (code "142") (name "unconnected-(D244-PadC)") (class "Default")
      (node (ref "D244") (pin "C") (pinfunction "C_C") (pintype "passive"))
    )
    (net (code "143") (name "unconnected-(D245-PadA)") (class "Default")
      (node (ref "D245") (pin "A") (pinfunction "A_A") (pintype "passive"))
    )
    (net (code "144") (name "unconnected-(D245-PadC)") (class "Default")
      (node (ref "D245") (pin "C") (pinfunction "C_C") (pintype "passive"))
    )
    (net (code "145") (name "unconnected-(D246-PadA)") (class "Default")
      (node (ref "D246") (pin "A") (pinfunction "A_A") (pintype "passive"))
    )
    (net (code "146") (name "unconnected-(D246-PadC)") (class "Default")
      (node (ref "D246") (pin "C") (pinfunction "C_C") (pintype "passive"))
    )
    (net (code "147") (name "unconnected-(D247-PadA)") (class "Default")
      (node (ref "D247") (pin "A") (pinfunction "A_A") (pintype "passive"))
    )
    (net (code "148") (name "unconnected-(D247-PadC)") (class "Default")
      (node (ref "D247") (pin "C") (pinfunction "C_C") (pintype "passive"))
    )
    (net (code "149") (name "unconnected-(D248-PadA)") (class "Default")
      (node (ref "D248") (pin "A") (pinfunction "A_A") (pintype "passive"))
    )
    (net (code "150") (name "unconnected-(D248-PadC)") (class "Default")
      (node (ref "D248") (pin "C") (pinfunction "C_C") (pintype "passive"))
    )
    (net (code "151") (name "unconnected-(D249-PadA)") (class "Default")
      (node (ref "D249") (pin "A") (pinfunction "A_A") (pintype "passive"))
    )
    (net (code "152") (name "unconnected-(D249-PadC)") (class "Default")
      (node (ref "D249") (pin "C") (pinfunction "C_C") (pintype "passive"))
    )
    (net (code "153") (name "unconnected-(D250-PadA)") (class "Default")
      (node (ref "D250") (pin "A") (pinfunction "A_A") (pintype "passive"))
    )
    (net (code "154") (name "unconnected-(D250-PadC)") (class "Default")
      (node (ref "D250") (pin "C") (pinfunction "C_C") (pintype "passive"))
    )
    (net (code "155") (name "unconnected-(D251-PadA)") (class "Default")
      (node (ref "D251") (pin "A") (pinfunction "A_A") (pintype "passive"))
    )
    (net (code "156") (name "unconnected-(D251-PadC)") (class "Default")
      (node (ref "D251") (pin "C") (pinfunction "C_C") (pintype "passive"))
    )
    (net (code "157") (name "unconnected-(D252-PadA)") (class "Default")
      (node (ref "D252") (pin "A") (pinfunction "A_A") (pintype "passive"))
    )
    (net (code "158") (name "unconnected-(D252-PadC)") (class "Default")
      (node (ref "D252") (pin "C") (pinfunction "C_C") (pintype "passive"))
    )
    (net (code "159") (name "unconnected-(D253-PadA)") (class "Default")
      (node (ref "D253") (pin "A") (pinfunction "A_A") (pintype "passive"))
    )
    (net (code "160") (name "unconnected-(D253-PadC)") (class "Default")
      (node (ref "D253") (pin "C") (pinfunction "C_C") (pintype "passive"))
    )
    (net (code "161") (name "unconnected-(D254-PadA)") (class "Default")
      (node (ref "D254") (pin "A") (pinfunction "A_A") (pintype "passive"))
    )
    (net (code "162") (name "unconnected-(D254-PadC)") (class "Default")
      (node (ref "D254") (pin "C") (pinfunction "C_C") (pintype "passive"))
    )
    (net (code "163") (name "unconnected-(D255-PadA)") (class "Default")
      (node (ref "D255") (pin "A") (pinfunction "A_A") (pintype "passive"))
    )
    (net (code "164") (name "unconnected-(D255-PadC)") (class "Default")
      (node (ref "D255") (pin "C") (pinfunction "C_C") (pintype "passive"))
    )
    (net (code "165") (name "unconnected-(D256-PadA)") (class "Default")
      (node (ref "D256") (pin "A") (pinfunction "A_A") (pintype "passive"))
    )
    (net (code "166") (name "unconnected-(D256-PadC)") (class "Default")
      (node (ref "D256") (pin "C") (pinfunction "C_C") (pintype "passive"))
    )
    (net (code "167") (name "unconnected-(D257-PadA)") (class "Default")
      (node (ref "D257") (pin "A") (pinfunction "A_A") (pintype "passive"))
    )
    (net (code "168") (name "unconnected-(D257-PadC)") (class "Default")
      (node (ref "D257") (pin "C") (pinfunction "C_C") (pintype "passive"))
    )
    (net (code "169") (name "unconnected-(D258-PadA)") (class "Default")
      (node (ref "D258") (pin "A") (pinfunction "A_A") (pintype "passive"))
    )
    (net (code "170") (name "unconnected-(D258-PadC)") (class "Default")
      (node (ref "D258") (pin "C") (pinfunction "C_C") (pintype "passive"))
    )
    (net (code "171") (name "unconnected-(D259-PadA)") (class "Default")
      (node (ref "D259") (pin "A") (pinfunction "A_A") (pintype "passive"))
    )
    (net (code "172") (name "unconnected-(D259-PadC)") (class "Default")
      (node (ref "D259") (pin "C") (pinfunction "C_C") (pintype "passive"))
    )
    (net (code "173") (name "unconnected-(D300-PadA)") (class "Default")
      (node (ref "D300") (pin "A") (pinfunction "A_A") (pintype "passive"))
    )
    (net (code "174") (name "unconnected-(D300-PadC)") (class "Default")
      (node (ref "D300") (pin "C") (pinfunction "C_C") (pintype "passive"))
    )
    (net (code "175") (name "unconnected-(D301-PadA)") (class "Default")
      (node (ref "D301") (pin "A") (pinfunction "A_A") (pintype "passive"))
    )
    (net (code "176") (name "unconnected-(D301-PadC)") (class "Default")
      (node (ref "D301") (pin "C") (pinfunction "C_C") (pintype "passive"))
    )
    (net (code "177") (name "unconnected-(D302-PadA)") (class "Default")
      (node (ref "D302") (pin "A") (pinfunction "A_A") (pintype "passive"))
    )
    (net (code "178") (name "unconnected-(D302-PadC)") (class "Default")
      (node (ref "D302") (pin "C") (pinfunction "C_C") (pintype "passive"))
    )
    (net (code "179") (name "unconnected-(D303-PadA)") (class "Default")
      (node (ref "D303") (pin "A") (pinfunction "A_A") (pintype "passive"))
    )
    (net (code "180") (name "unconnected-(D303-PadC)") (class "Default")
      (node (ref "D303") (pin "C") (pinfunction "C_C") (pintype "passive"))
    )
    (net (code "181") (name "unconnected-(D304-PadA)") (class "Default")
      (node (ref "D304") (pin "A") (pinfunction "A_A") (pintype "passive"))
    )
    (net (code "182") (name "unconnected-(D304-PadC)") (class "Default")
      (node (ref "D304") (pin "C") (pinfunction "C_C") (pintype "passive"))
    )
    (net (code "183") (name "unconnected-(D305-PadA)") (class "Default")
      (node (ref "D305") (pin "A") (pinfunction "A_A") (pintype "passive"))
    )
    (net (code "184") (name "unconnected-(D305-PadC)") (class "Default")
      (node (ref "D305") (pin "C") (pinfunction "C_C") (pintype "passive"))
    )
    (net (code "185") (name "unconnected-(D306-PadA)") (class "Default")
      (node (ref "D306") (pin "A") (pinfunction "A_A") (pintype "passive"))
    )
    (net (code "186") (name "unconnected-(D306-PadC)") (class "Default")
      (node (ref "D306") (pin "C") (pinfunction "C_C") (pintype "passive"))
    )
    (net (code "187") (name "unconnected-(D307-PadA)") (class "Default")
      (node (ref "D307") (pin "A") (pinfunction "A_A") (pintype "passive"))
    )
    (net (code "188") (name "unconnected-(D307-PadC)") (class "Default")
      (node (ref "D307") (pin "C") (pinfunction "C_C") (pintype "passive"))
    )
    (net (code "189") (name "unconnected-(D308-PadA)") (class "Default")
      (node (ref "D308") (pin "A") (pinfunction "A_A") (pintype "passive"))
    )
    (net (code "190") (name "unconnected-(D308-PadC)") (class "Default")
      (node (ref "D308") (pin "C") (pinfunction "C_C") (pintype "passive"))
    )
    (net (code "191") (name "unconnected-(D309-PadA)") (class "Default")
      (node (ref "D309") (pin "A") (pinfunction "A_A") (pintype "passive"))
    )
    (net (code "192") (name "unconnected-(D309-PadC)") (class "Default")
      (node (ref "D309") (pin "C") (pinfunction "C_C") (pintype "passive"))
    )
    (net (code "193") (name "unconnected-(D310-PadA)") (class "Default")
      (node (ref "D310") (pin "A") (pinfunction "A_A") (pintype "passive"))
    )
    (net (code "194") (name "unconnected-(D310-PadC)") (class "Default")
      (node (ref "D310") (pin "C") (pinfunction "C_C") (pintype "passive"))
    )
    (net (code "195") (name "unconnected-(D311-PadA)") (class "Default")
      (node (ref "D311") (pin "A") (pinfunction "A_A") (pintype "passive"))
    )
    (net (code "196") (name "unconnected-(D311-PadC)") (class "Default")
      (node (ref "D311") (pin "C") (pinfunction "C_C") (pintype "passive"))
    )
    (net (code "197") (name "unconnected-(D312-PadA)") (class "Default")
      (node (ref "D312") (pin "A") (pinfunction "A_A") (pintype "passive"))
    )
    (net (code "198") (name "unconnected-(D312-PadC)") (class "Default")
      (node (ref "D312") (pin "C") (pinfunction "C_C") (pintype "passive"))
    )
    (net (code "199") (name "unconnected-(D313-PadA)") (class "Default")
      (node (ref "D313") (pin "A") (pinfunction "A_A") (pintype "passive"))
    )
    (net (code "200") (name "unconnected-(D313-PadC)") (class "Default")
      (node (ref "D313") (pin "C") (pinfunction "C_C") (pintype "passive"))
    )
    (net (code "201") (name "unconnected-(D314-PadA)") (class "Default")
      (node (ref "D314") (pin "A") (pinfunction "A_A") (pintype "passive"))
    )
    (net (code "202") (name "unconnected-(D314-PadC)") (class "Default")
      (node (ref "D314") (pin "C") (pinfunction "C_C") (pintype "passive"))
    )
    (net (code "203") (name "unconnected-(D315-PadA)") (class "Default")
      (node (ref "D315") (pin "A") (pinfunction "A_A") (pintype "passive"))
    )
    (net (code "204") (name "unconnected-(D315-PadC)") (class "Default")
      (node (ref "D315") (pin "C") (pinfunction "C_C") (pintype "passive"))
    )
    (net (code "205") (name "unconnected-(D316-PadA)") (class "Default")
      (node (ref "D316") (pin "A") (pinfunction "A_A") (pintype "passive"))
    )
    (net (code "206") (name "unconnected-(D316-PadC)") (class "Default")
      (node (ref "D316") (pin "C") (pinfunction "C_C") (pintype "passive"))
    )
    (net (code "207") (name "unconnected-(D317-PadA)") (class "Default")
      (node (ref "D317") (pin "A") (pinfunction "A_A") (pintype "passive"))
    )
    (net (code "208") (name "unconnected-(D317-PadC)") (class "Default")
      (node (ref "D317") (pin "C") (pinfunction "C_C") (pintype "passive"))
    )
    (net (code "209") (name "unconnected-(D318-PadA)") (class "Default")
      (node (ref "D318") (pin "A") (pinfunction "A_A") (pintype "passive"))
    )
    (net (code "210") (name "unconnected-(D318-PadC)") (class "Default")
      (node (ref "D318") (pin "C") (pinfunction "C_C") (pintype "passive"))
    )
    (net (code "211") (name "unconnected-(D319-PadA)") (class "Default")
      (node (ref "D319") (pin "A") (pinfunction "A_A") (pintype "passive"))
    )
    (net (code "212") (name "unconnected-(D319-PadC)") (class "Default")
      (node (ref "D319") (pin "C") (pinfunction "C_C") (pintype "passive"))
    )
    (net (code "213") (name "unconnected-(D320-PadA)") (class "Default")
      (node (ref "D320") (pin "A") (pinfunction "A_A") (pintype "passive"))
    )
    (net (code "214") (name "unconnected-(D320-PadC)") (class "Default")
      (node (ref "D320") (pin "C") (pinfunction "C_C") (pintype "passive"))
    )
    (net (code "215") (name "unconnected-(D321-PadA)") (class "Default")
      (node (ref "D321") (pin "A") (pinfunction "A_A") (pintype "passive"))
    )
    (net (code "216") (name "unconnected-(D321-PadC)") (class "Default")
      (node (ref "D321") (pin "C") (pinfunction "C_C") (pintype "passive"))
    )
    (net (code "217") (name "unconnected-(D322-PadA)") (class "Default")
      (node (ref "D322") (pin "A") (pinfunction "A_A") (pintype "passive"))
    )
    (net (code "218") (name "unconnected-(D322-PadC)") (class "Default")
      (node (ref "D322") (pin "C") (pinfunction "C_C") (pintype "passive"))
    )
    (net (code "219") (name "unconnected-(D323-PadA)") (class "Default")
      (node (ref "D323") (pin "A") (pinfunction "A_A") (pintype "passive"))
    )
    (net (code "220") (name "unconnected-(D323-PadC)") (class "Default")
      (node (ref "D323") (pin "C") (pinfunction "C_C") (pintype "passive"))
    )
    (net (code "221") (name "unconnected-(D324-PadA)") (class "Default")
      (node (ref "D324") (pin "A") (pinfunction "A_A") (pintype "passive"))
    )
    (net (code "222") (name "unconnected-(D324-PadC)") (class "Default")
      (node (ref "D324") (pin "C") (pinfunction "C_C") (pintype "passive"))
    )
    (net (code "223") (name "unconnected-(D325-PadA)") (class "Default")
      (node (ref "D325") (pin "A") (pinfunction "A_A") (pintype "passive"))
    )
    (net (code "224") (name "unconnected-(D325-PadC)") (class "Default")
      (node (ref "D325") (pin "C") (pinfunction "C_C") (pintype "passive"))
    )
    (net (code "225") (name "unconnected-(D326-PadA)") (class "Default")
      (node (ref "D326") (pin "A") (pinfunction "A_A") (pintype "passive"))
    )
    (net (code "226") (name "unconnected-(D326-PadC)") (class "Default")
      (node (ref "D326") (pin "C") (pinfunction "C_C") (pintype "passive"))
    )
    (net (code "227") (name "unconnected-(D327-PadA)") (class "Default")
      (node (ref "D327") (pin "A") (pinfunction "A_A") (pintype "passive"))
    )
    (net (code "228") (name "unconnected-(D327-PadC)") (class "Default")
      (node (ref "D327") (pin "C") (pinfunction "C_C") (pintype "passive"))
    )
    (net (code "229") (name "unconnected-(D328-PadA)") (class "Default")
      (node (ref "D328") (pin "A") (pinfunction "A_A") (pintype "passive"))
    )
    (net (code "230") (name "unconnected-(D328-PadC)") (class "Default")
      (node (ref "D328") (pin "C") (pinfunction "C_C") (pintype "passive"))
    )
    (net (code "231") (name "unconnected-(D329-PadA)") (class "Default")
      (node (ref "D329") (pin "A") (pinfunction "A_A") (pintype "passive"))
    )
    (net (code "232") (name "unconnected-(D329-PadC)") (class "Default")
      (node (ref "D329") (pin "C") (pinfunction "C_C") (pintype "passive"))
    )
    (net (code "233") (name "unconnected-(D330-PadA)") (class "Default")
      (node (ref "D330") (pin "A") (pinfunction "A_A") (pintype "passive"))
    )
    (net (code "234") (name "unconnected-(D330-PadC)") (class "Default")
      (node (ref "D330") (pin "C") (pinfunction "C_C") (pintype "passive"))
    )
    (net (code "235") (name "unconnected-(D331-PadA)") (class "Default")
      (node (ref "D331") (pin "A") (pinfunction "A_A") (pintype "passive"))
    )
    (net (code "236") (name "unconnected-(D331-PadC)") (class "Default")
      (node (ref "D331") (pin "C") (pinfunction "C_C") (pintype "passive"))
    )
    (net (code "237") (name "unconnected-(D332-PadA)") (class "Default")
      (node (ref "D332") (pin "A") (pinfunction "A_A") (pintype "passive"))
    )
    (net (code "238") (name "unconnected-(D332-PadC)") (class "Default")
      (node (ref "D332") (pin "C") (pinfunction "C_C") (pintype "passive"))
    )
    (net (code "239") (name "unconnected-(D333-PadA)") (class "Default")
      (node (ref "D333") (pin "A") (pinfunction "A_A") (pintype "passive"))
    )
    (net (code "240") (name "unconnected-(D333-PadC)") (class "Default")
      (node (ref "D333") (pin "C") (pinfunction "C_C") (pintype "passive"))
    )
    (net (code "241") (name "unconnected-(D334-PadA)") (class "Default")
      (node (ref "D334") (pin "A") (pinfunction "A_A") (pintype "passive"))
    )
    (net (code "242") (name "unconnected-(D334-PadC)") (class "Default")
      (node (ref "D334") (pin "C") (pinfunction "C_C") (pintype "passive"))
    )
    (net (code "243") (name "unconnected-(D335-PadA)") (class "Default")
      (node (ref "D335") (pin "A") (pinfunction "A_A") (pintype "passive"))
    )
    (net (code "244") (name "unconnected-(D335-PadC)") (class "Default")
      (node (ref "D335") (pin "C") (pinfunction "C_C") (pintype "passive"))
    )
    (net (code "245") (name "unconnected-(D336-PadA)") (class "Default")
      (node (ref "D336") (pin "A") (pinfunction "A_A") (pintype "passive"))
    )
    (net (code "246") (name "unconnected-(D336-PadC)") (class "Default")
      (node (ref "D336") (pin "C") (pinfunction "C_C") (pintype "passive"))
    )
    (net (code "247") (name "unconnected-(D337-PadA)") (class "Default")
      (node (ref "D337") (pin "A") (pinfunction "A_A") (pintype "passive"))
    )
    (net (code "248") (name "unconnected-(D337-PadC)") (class "Default")
      (node (ref "D337") (pin "C") (pinfunction "C_C") (pintype "passive"))
    )
    (net (code "249") (name "unconnected-(D338-PadA)") (class "Default")
      (node (ref "D338") (pin "A") (pinfunction "A_A") (pintype "passive"))
    )
    (net (code "250") (name "unconnected-(D338-PadC)") (class "Default")
      (node (ref "D338") (pin "C") (pinfunction "C_C") (pintype "passive"))
    )
    (net (code "251") (name "unconnected-(D339-PadA)") (class "Default")
      (node (ref "D339") (pin "A") (pinfunction "A_A") (pintype "passive"))
    )
    (net (code "252") (name "unconnected-(D339-PadC)") (class "Default")
      (node (ref "D339") (pin "C") (pinfunction "C_C") (pintype "passive"))
    )
    (net (code "253") (name "unconnected-(D340-PadA)") (class "Default")
      (node (ref "D340") (pin "A") (pinfunction "A_A") (pintype "passive"))
    )
    (net (code "254") (name "unconnected-(D340-PadC)") (class "Default")
      (node (ref "D340") (pin "C") (pinfunction "C_C") (pintype "passive"))
    )
    (net (code "255") (name "unconnected-(D341-PadA)") (class "Default")
      (node (ref "D341") (pin "A") (pinfunction "A_A") (pintype "passive"))
    )
    (net (code "256") (name "unconnected-(D341-PadC)") (class "Default")
      (node (ref "D341") (pin "C") (pinfunction "C_C") (pintype "passive"))
    )
    (net (code "257") (name "unconnected-(D342-PadA)") (class "Default")
      (node (ref "D342") (pin "A") (pinfunction "A_A") (pintype "passive"))
    )
    (net (code "258") (name "unconnected-(D342-PadC)") (class "Default")
      (node (ref "D342") (pin "C") (pinfunction "C_C") (pintype "passive"))
    )
    (net (code "259") (name "unconnected-(D343-PadA)") (class "Default")
      (node (ref "D343") (pin "A") (pinfunction "A_A") (pintype "passive"))
    )
    (net (code "260") (name "unconnected-(D343-PadC)") (class "Default")
      (node (ref "D343") (pin "C") (pinfunction "C_C") (pintype "passive"))
    )
    (net (code "261") (name "unconnected-(D344-PadA)") (class "Default")
      (node (ref "D344") (pin "A") (pinfunction "A_A") (pintype "passive"))
    )
    (net (code "262") (name "unconnected-(D344-PadC)") (class "Default")
      (node (ref "D344") (pin "C") (pinfunction "C_C") (pintype "passive"))
    )
    (net (code "263") (name "unconnected-(D345-PadA)") (class "Default")
      (node (ref "D345") (pin "A") (pinfunction "A_A") (pintype "passive"))
    )
    (net (code "264") (name "unconnected-(D345-PadC)") (class "Default")
      (node (ref "D345") (pin "C") (pinfunction "C_C") (pintype "passive"))
    )
    (net (code "265") (name "unconnected-(D346-PadA)") (class "Default")
      (node (ref "D346") (pin "A") (pinfunction "A_A") (pintype "passive"))
    )
    (net (code "266") (name "unconnected-(D346-PadC)") (class "Default")
      (node (ref "D346") (pin "C") (pinfunction "C_C") (pintype "passive"))
    )
    (net (code "267") (name "unconnected-(D347-PadA)") (class "Default")
      (node (ref "D347") (pin "A") (pinfunction "A_A") (pintype "passive"))
    )
    (net (code "268") (name "unconnected-(D347-PadC)") (class "Default")
      (node (ref "D347") (pin "C") (pinfunction "C_C") (pintype "passive"))
    )
    (net (code "269") (name "unconnected-(D348-PadA)") (class "Default")
      (node (ref "D348") (pin "A") (pinfunction "A_A") (pintype "passive"))
    )
    (net (code "270") (name "unconnected-(D348-PadC)") (class "Default")
      (node (ref "D348") (pin "C") (pinfunction "C_C") (pintype "passive"))
    )
    (net (code "271") (name "unconnected-(D349-PadA)") (class "Default")
      (node (ref "D349") (pin "A") (pinfunction "A_A") (pintype "passive"))
    )
    (net (code "272") (name "unconnected-(D349-PadC)") (class "Default")
      (node (ref "D349") (pin "C") (pinfunction "C_C") (pintype "passive"))
    )
    (net (code "273") (name "unconnected-(D350-PadA)") (class "Default")
      (node (ref "D350") (pin "A") (pinfunction "A_A") (pintype "passive"))
    )
    (net (code "274") (name "unconnected-(D350-PadC)") (class "Default")
      (node (ref "D350") (pin "C") (pinfunction "C_C") (pintype "passive"))
    )
    (net (code "275") (name "unconnected-(D351-PadA)") (class "Default")
      (node (ref "D351") (pin "A") (pinfunction "A_A") (pintype "passive"))
    )
    (net (code "276") (name "unconnected-(D351-PadC)") (class "Default")
      (node (ref "D351") (pin "C") (pinfunction "C_C") (pintype "passive"))
    )
    (net (code "277") (name "unconnected-(D352-PadA)") (class "Default")
      (node (ref "D352") (pin "A") (pinfunction "A_A") (pintype "passive"))
    )
    (net (code "278") (name "unconnected-(D352-PadC)") (class "Default")
      (node (ref "D352") (pin "C") (pinfunction "C_C") (pintype "passive"))
    )
    (net (code "279") (name "unconnected-(D353-PadA)") (class "Default")
      (node (ref "D353") (pin "A") (pinfunction "A_A") (pintype "passive"))
    )
    (net (code "280") (name "unconnected-(D353-PadC)") (class "Default")
      (node (ref "D353") (pin "C") (pinfunction "C_C") (pintype "passive"))
    )
    (net (code "281") (name "unconnected-(D354-PadA)") (class "Default")
      (node (ref "D354") (pin "A") (pinfunction "A_A") (pintype "passive"))
    )
    (net (code "282") (name "unconnected-(D354-PadC)") (class "Default")
      (node (ref "D354") (pin "C") (pinfunction "C_C") (pintype "passive"))
    )
    (net (code "283") (name "unconnected-(D355-PadA)") (class "Default")
      (node (ref "D355") (pin "A") (pinfunction "A_A") (pintype "passive"))
    )
    (net (code "284") (name "unconnected-(D355-PadC)") (class "Default")
      (node (ref "D355") (pin "C") (pinfunction "C_C") (pintype "passive"))
    )
    (net (code "285") (name "unconnected-(D356-PadA)") (class "Default")
      (node (ref "D356") (pin "A") (pinfunction "A_A") (pintype "passive"))
    )
    (net (code "286") (name "unconnected-(D356-PadC)") (class "Default")
      (node (ref "D356") (pin "C") (pinfunction "C_C") (pintype "passive"))
    )
    (net (code "287") (name "unconnected-(D357-PadA)") (class "Default")
      (node (ref "D357") (pin "A") (pinfunction "A_A") (pintype "passive"))
    )
    (net (code "288") (name "unconnected-(D357-PadC)") (class "Default")
      (node (ref "D357") (pin "C") (pinfunction "C_C") (pintype "passive"))
    )
    (net (code "289") (name "unconnected-(D358-PadA)") (class "Default")
      (node (ref "D358") (pin "A") (pinfunction "A_A") (pintype "passive"))
    )
    (net (code "290") (name "unconnected-(D358-PadC)") (class "Default")
      (node (ref "D358") (pin "C") (pinfunction "C_C") (pintype "passive"))
    )
    (net (code "291") (name "unconnected-(D359-PadA)") (class "Default")
      (node (ref "D359") (pin "A") (pinfunction "A_A") (pintype "passive"))
    )
    (net (code "292") (name "unconnected-(D359-PadC)") (class "Default")
      (node (ref "D359") (pin "C") (pinfunction "C_C") (pintype "passive"))
    )
    (net (code "293") (name "unconnected-(U401-ADC6-Pad19)") (class "Default")
      (node (ref "U401") (pin "19") (pinfunction "ADC6_19") (pintype "bidirectional"))
    )
    (net (code "294") (name "unconnected-(U401-ADC7-Pad22)") (class "Default")
      (node (ref "U401") (pin "22") (pinfunction "ADC7_22") (pintype "bidirectional"))
    )
    (net (code "295") (name "unconnected-(U501-CTS-Pad11)") (class "Default")
      (node (ref "U501") (pin "11") (pinfunction "CTS_11") (pintype "input"))
    )
    (net (code "296") (name "unconnected-(U501-DCD-Pad10)") (class "Default")
      (node (ref "U501") (pin "10") (pinfunction "DCD_10") (pintype "input"))
    )
    (net (code "297") (name "unconnected-(U501-DSR-Pad9)") (class "Default")
      (node (ref "U501") (pin "9") (pinfunction "DSR_9") (pintype "input"))
    )
    (net (code "298") (name "unconnected-(U501-OSCI-Pad27)") (class "Default")
      (node (ref "U501") (pin "27") (pinfunction "OSCI_27") (pintype "input"))
    )
    (net (code "299") (name "unconnected-(U501-OSCO-Pad28)") (class "Default")
      (node (ref "U501") (pin "28") (pinfunction "OSCO_28") (pintype "output"))
    )
    (net (code "300") (name "unconnected-(U501-PWREN-Pad14)") (class "Default")
      (node (ref "U501") (pin "14") (pinfunction "PWREN_14") (pintype "input"))
    )
    (net (code "301") (name "unconnected-(U501-RESET-Pad19)") (class "Default")
      (node (ref "U501") (pin "19") (pinfunction "RESET_19") (pintype "input"))
    )
    (net (code "302") (name "unconnected-(U501-RI-Pad6)") (class "Default")
      (node (ref "U501") (pin "6") (pinfunction "RI_6") (pintype "input"))
    )
    (net (code "303") (name "unconnected-(U501-RTS-Pad3)") (class "Default")
      (node (ref "U501") (pin "3") (pinfunction "RTS_3") (pintype "output"))
    )
    (net (code "304") (name "unconnected-(U501-SLEEP-Pad12)") (class "Default")
      (node (ref "U501") (pin "12") (pinfunction "SLEEP_12") (pintype "input"))
    )
    (net (code "305") (name "unconnected-(U501-TXDEN-Pad13)") (class "Default")
      (node (ref "U501") (pin "13") (pinfunction "TXDEN_13") (pintype "input"))
    )
  )
)
